# rekick2015-Prototyp-Tests.net
KiCad netlist of a schematic drawn in EAGLE
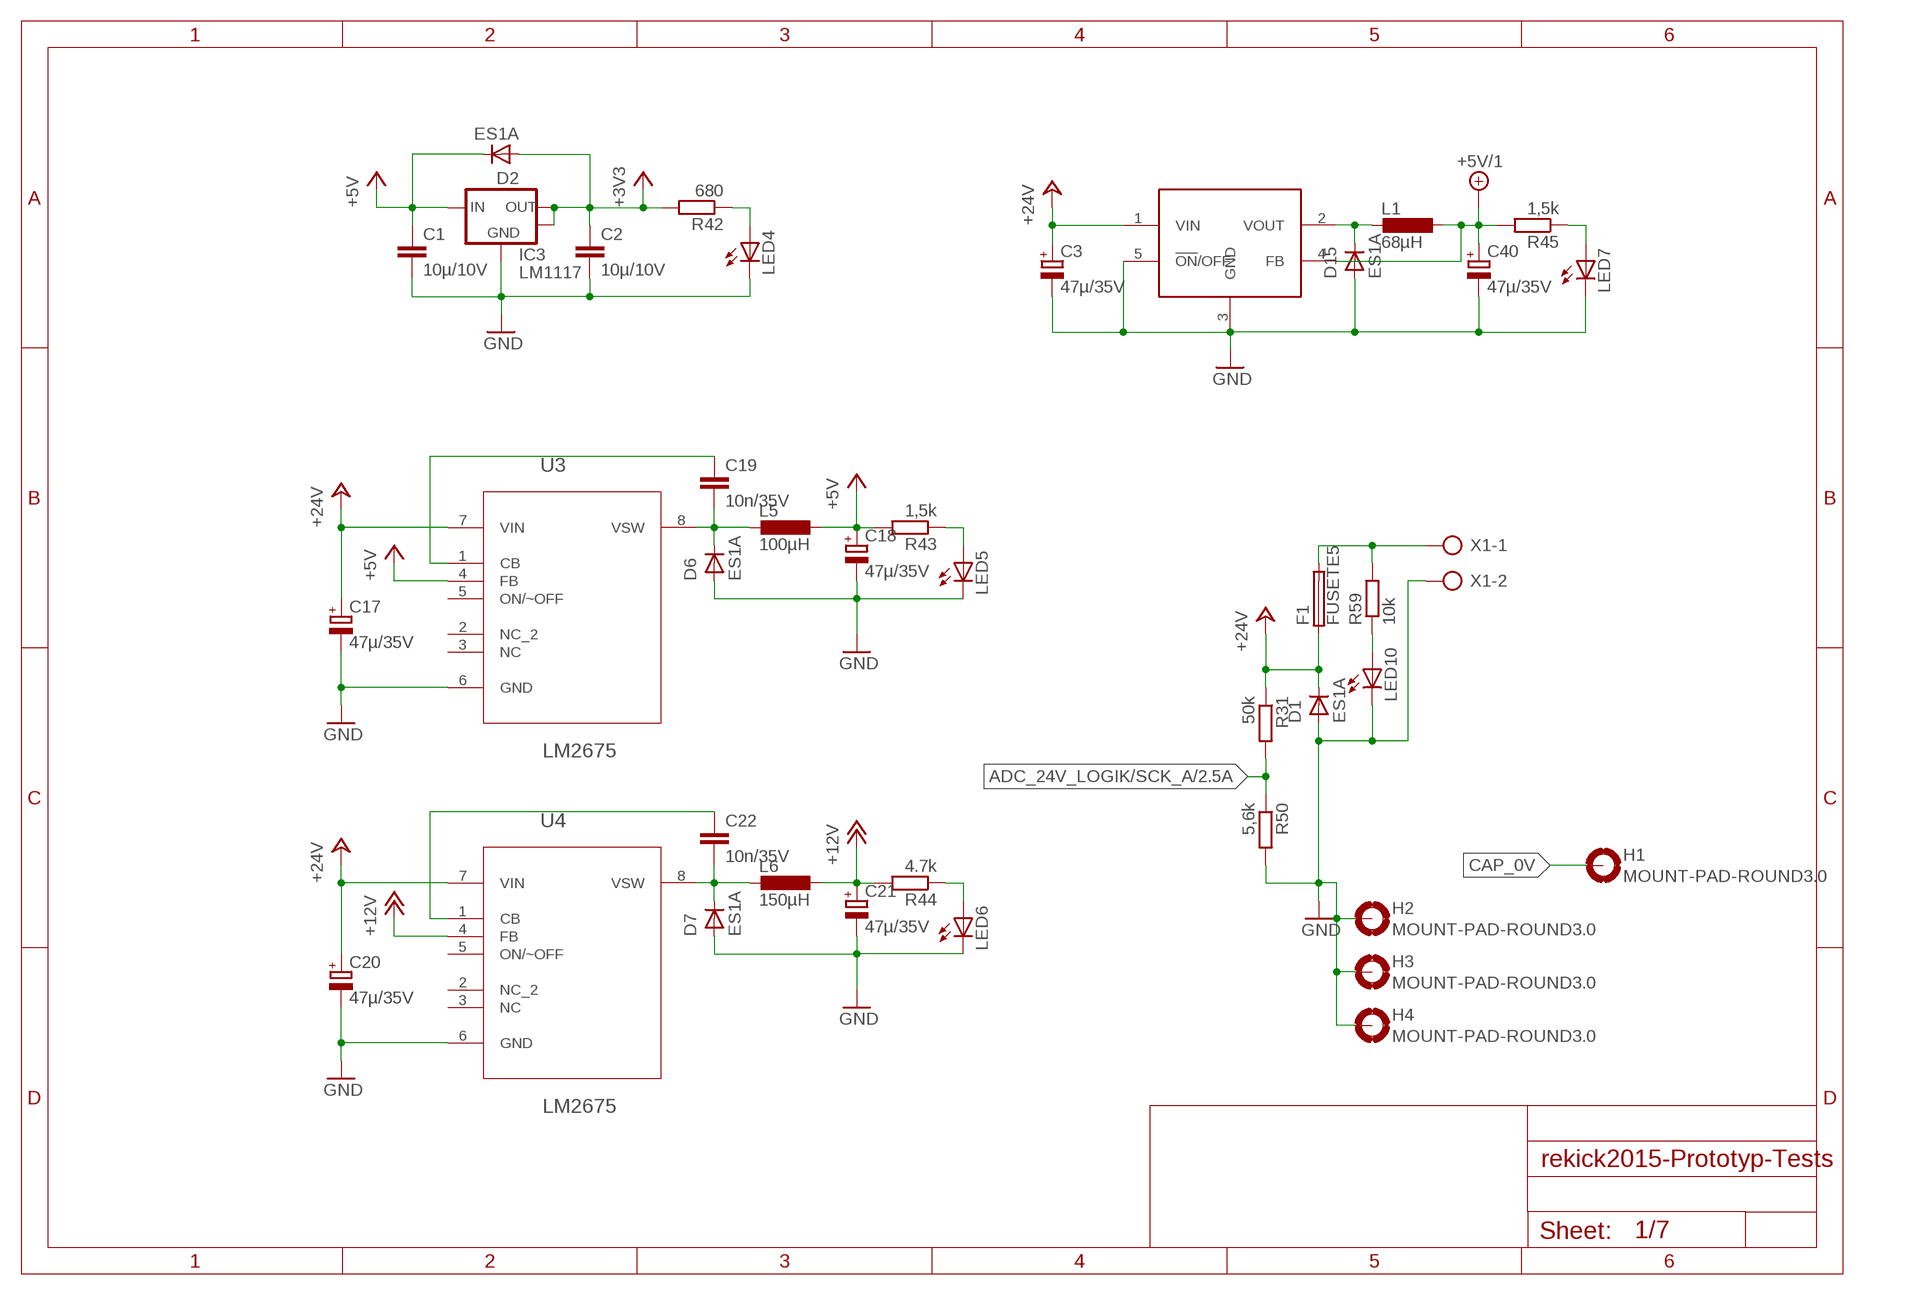
[diagram p0: schematic, sheet 1]
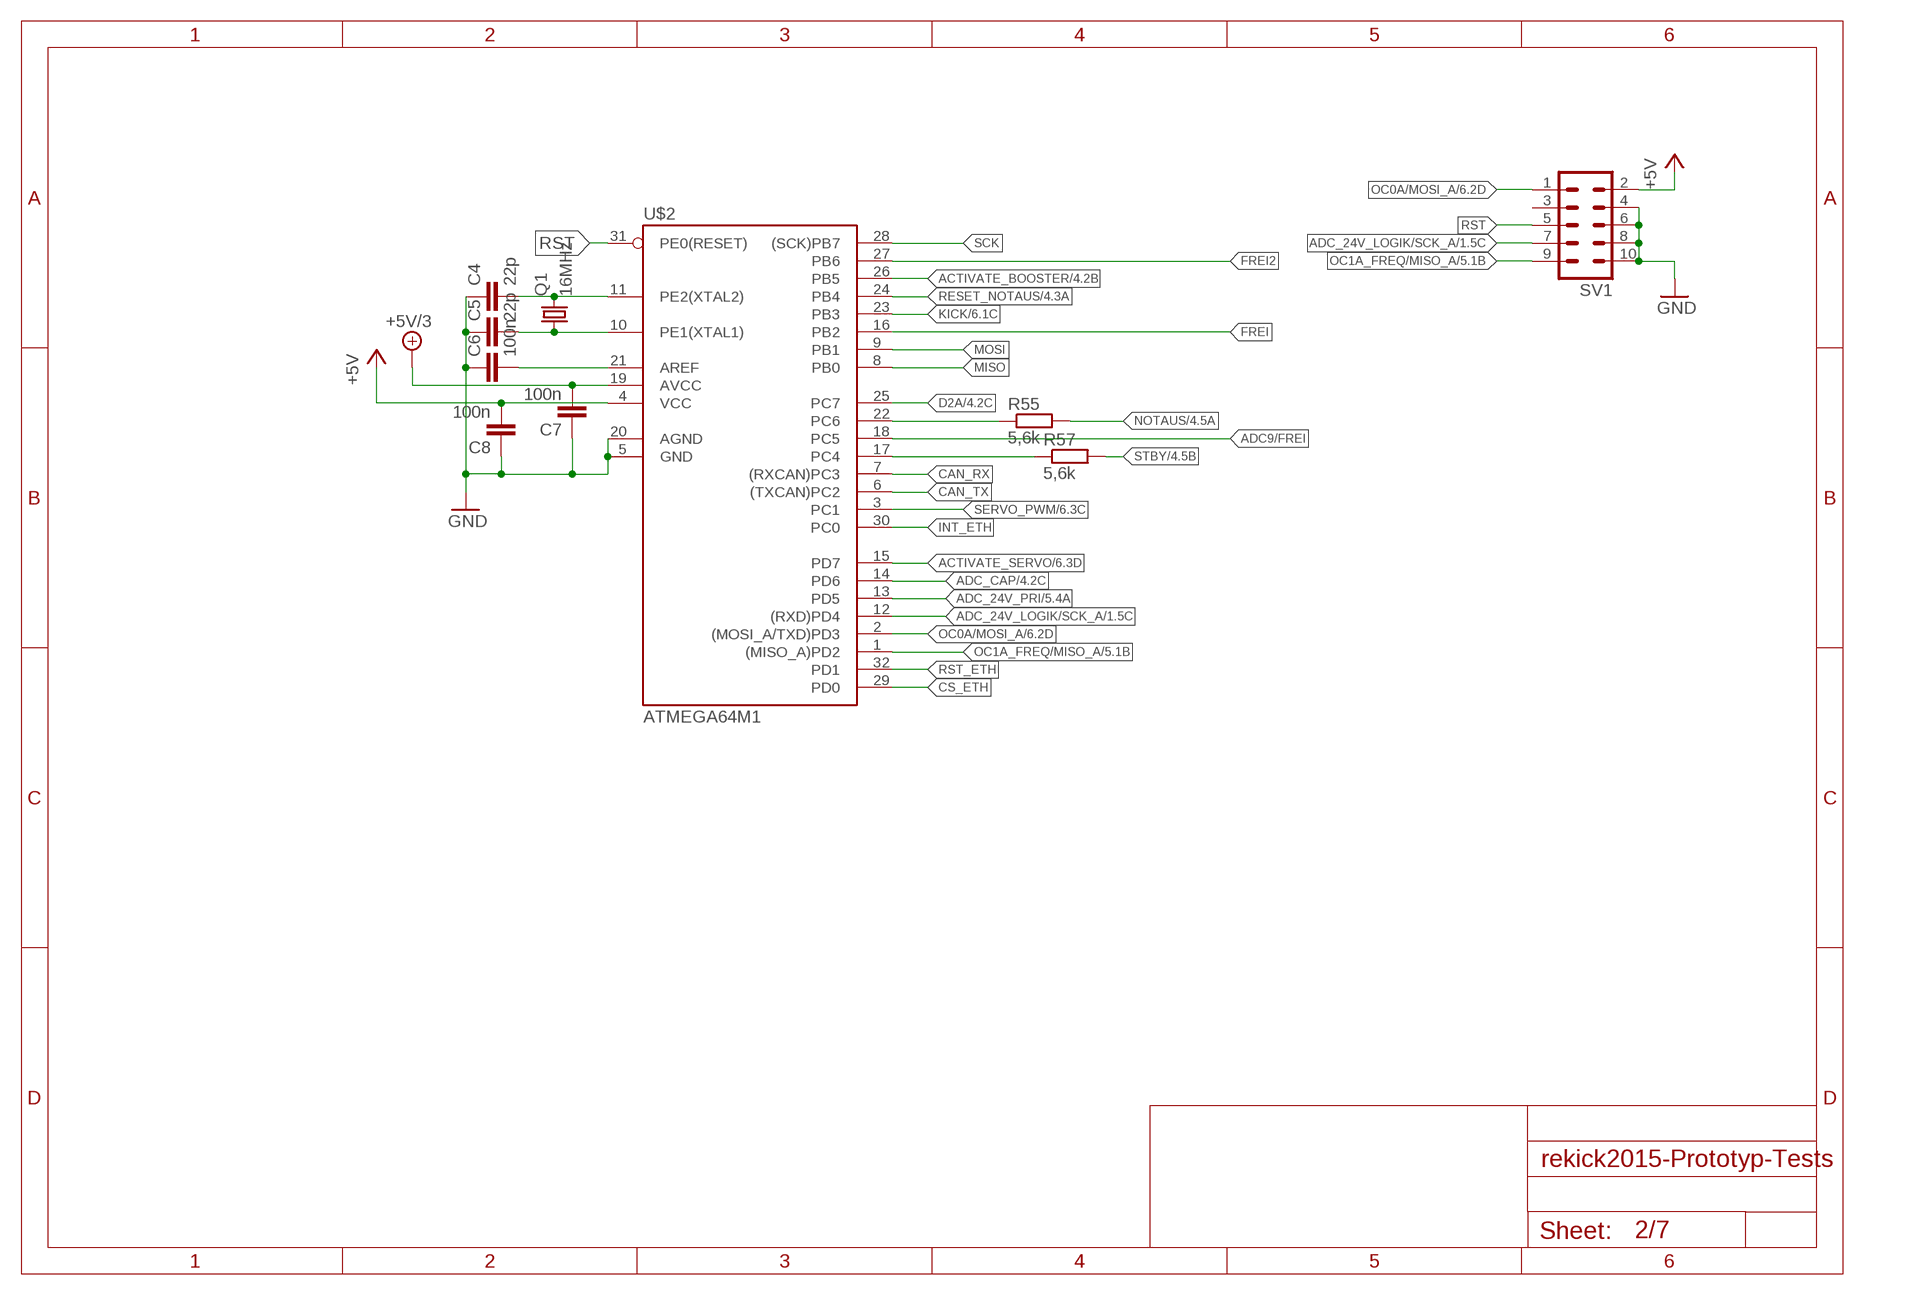
[diagram p1: schematic, sheet 2]
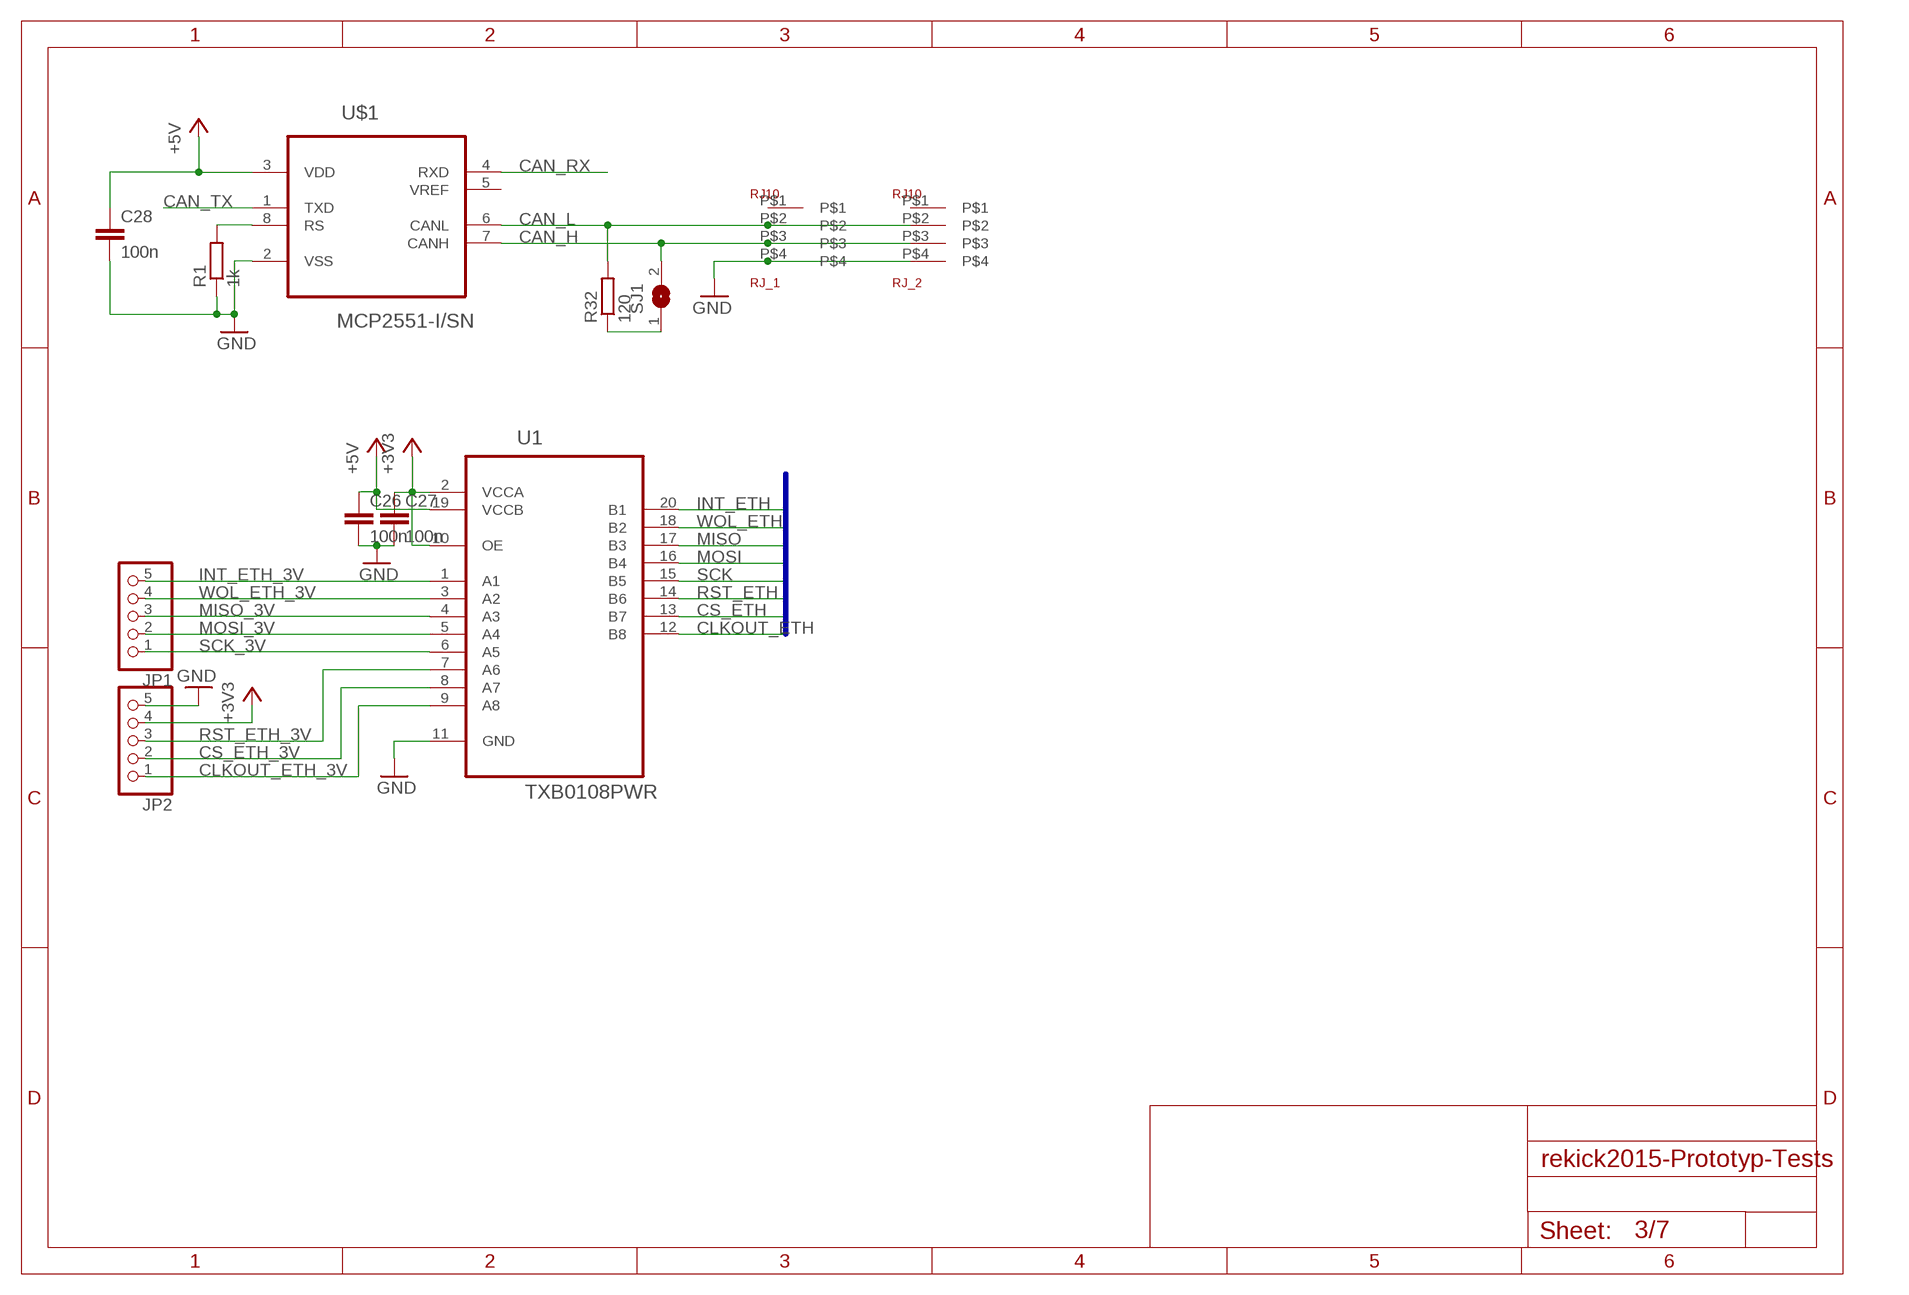
[diagram p2: schematic, sheet 3]
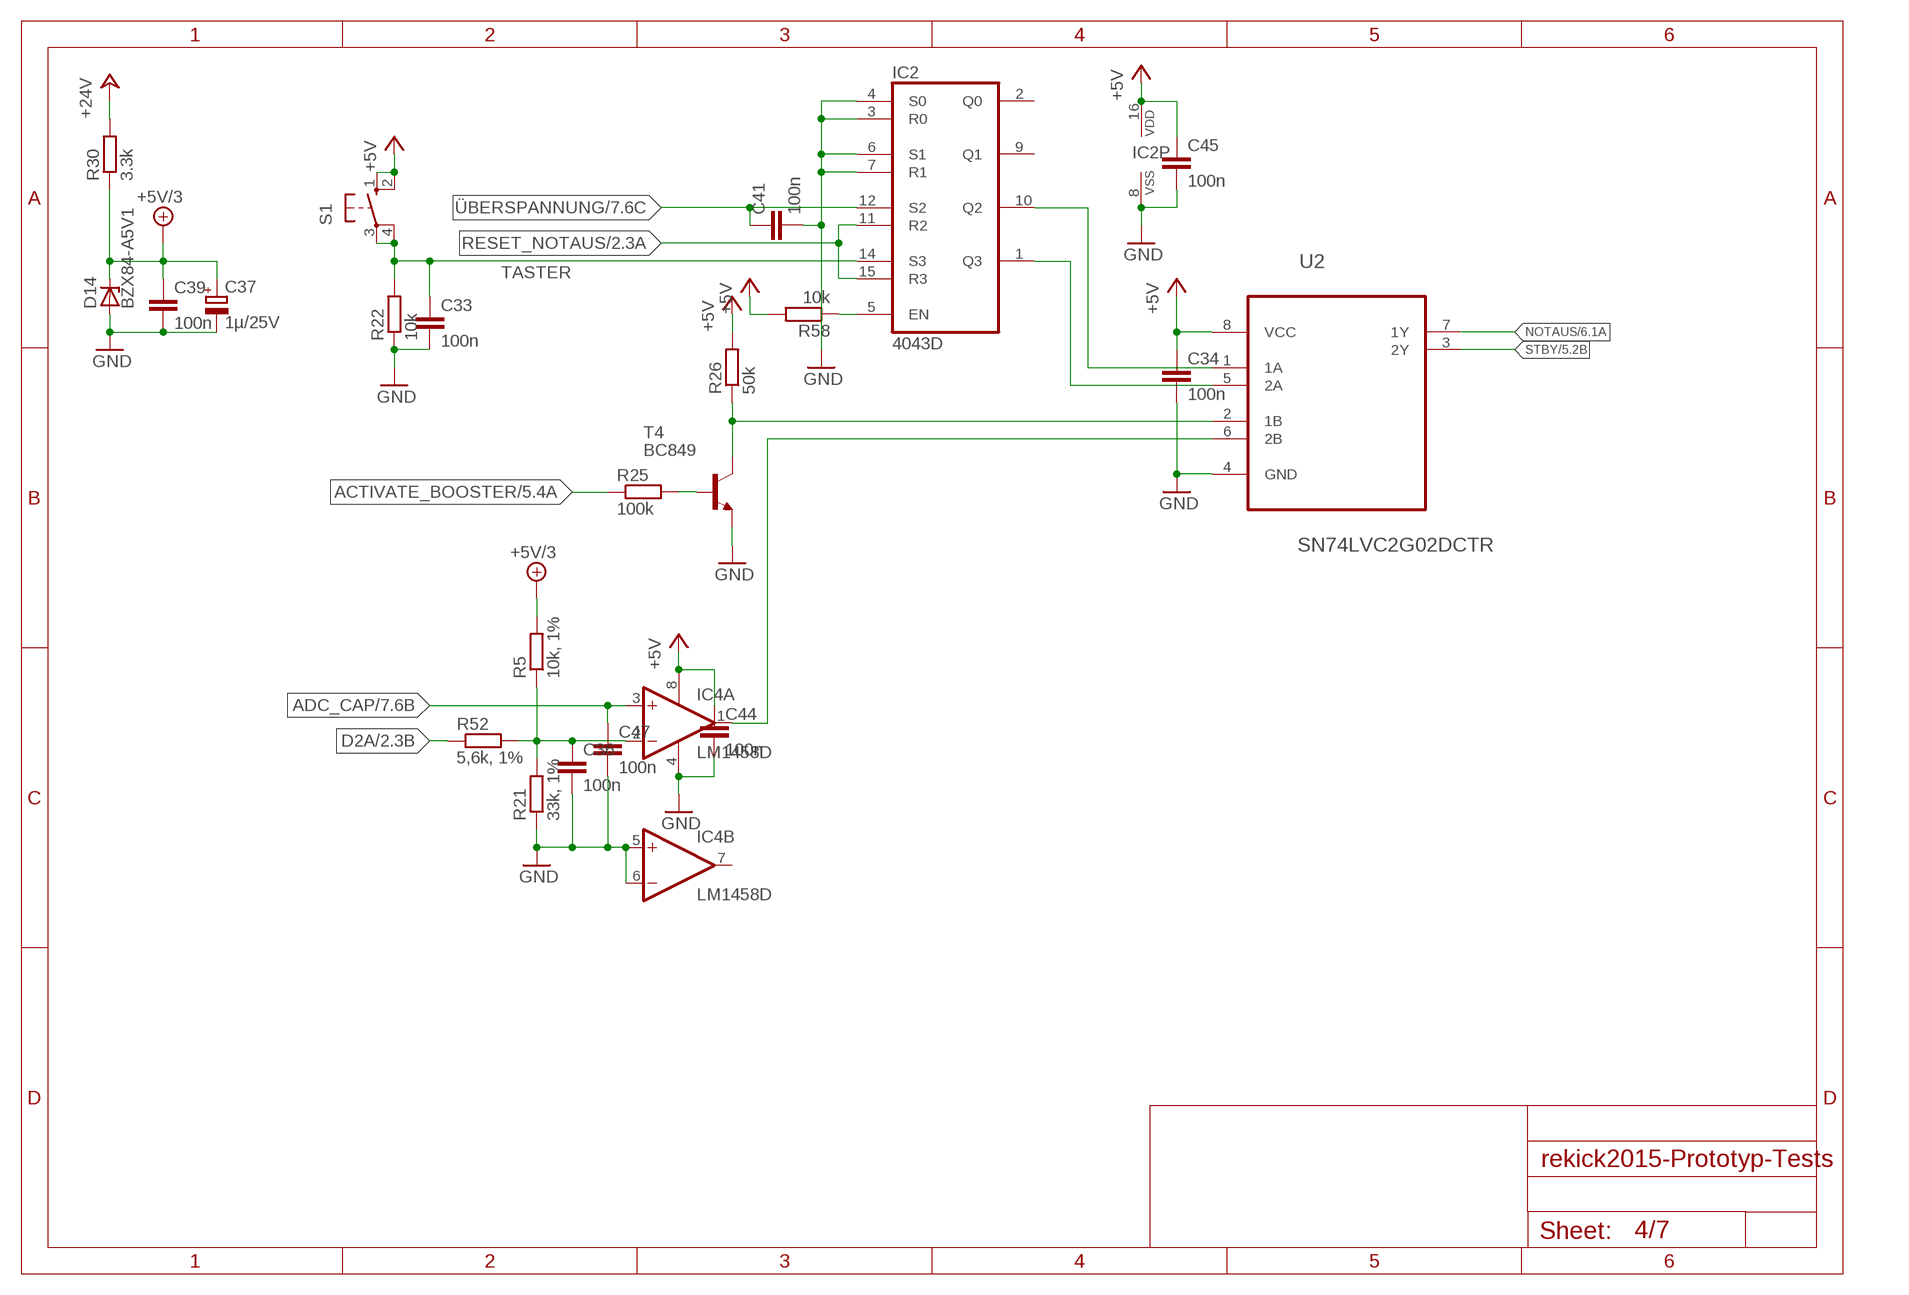
[diagram p3: schematic, sheet 4]
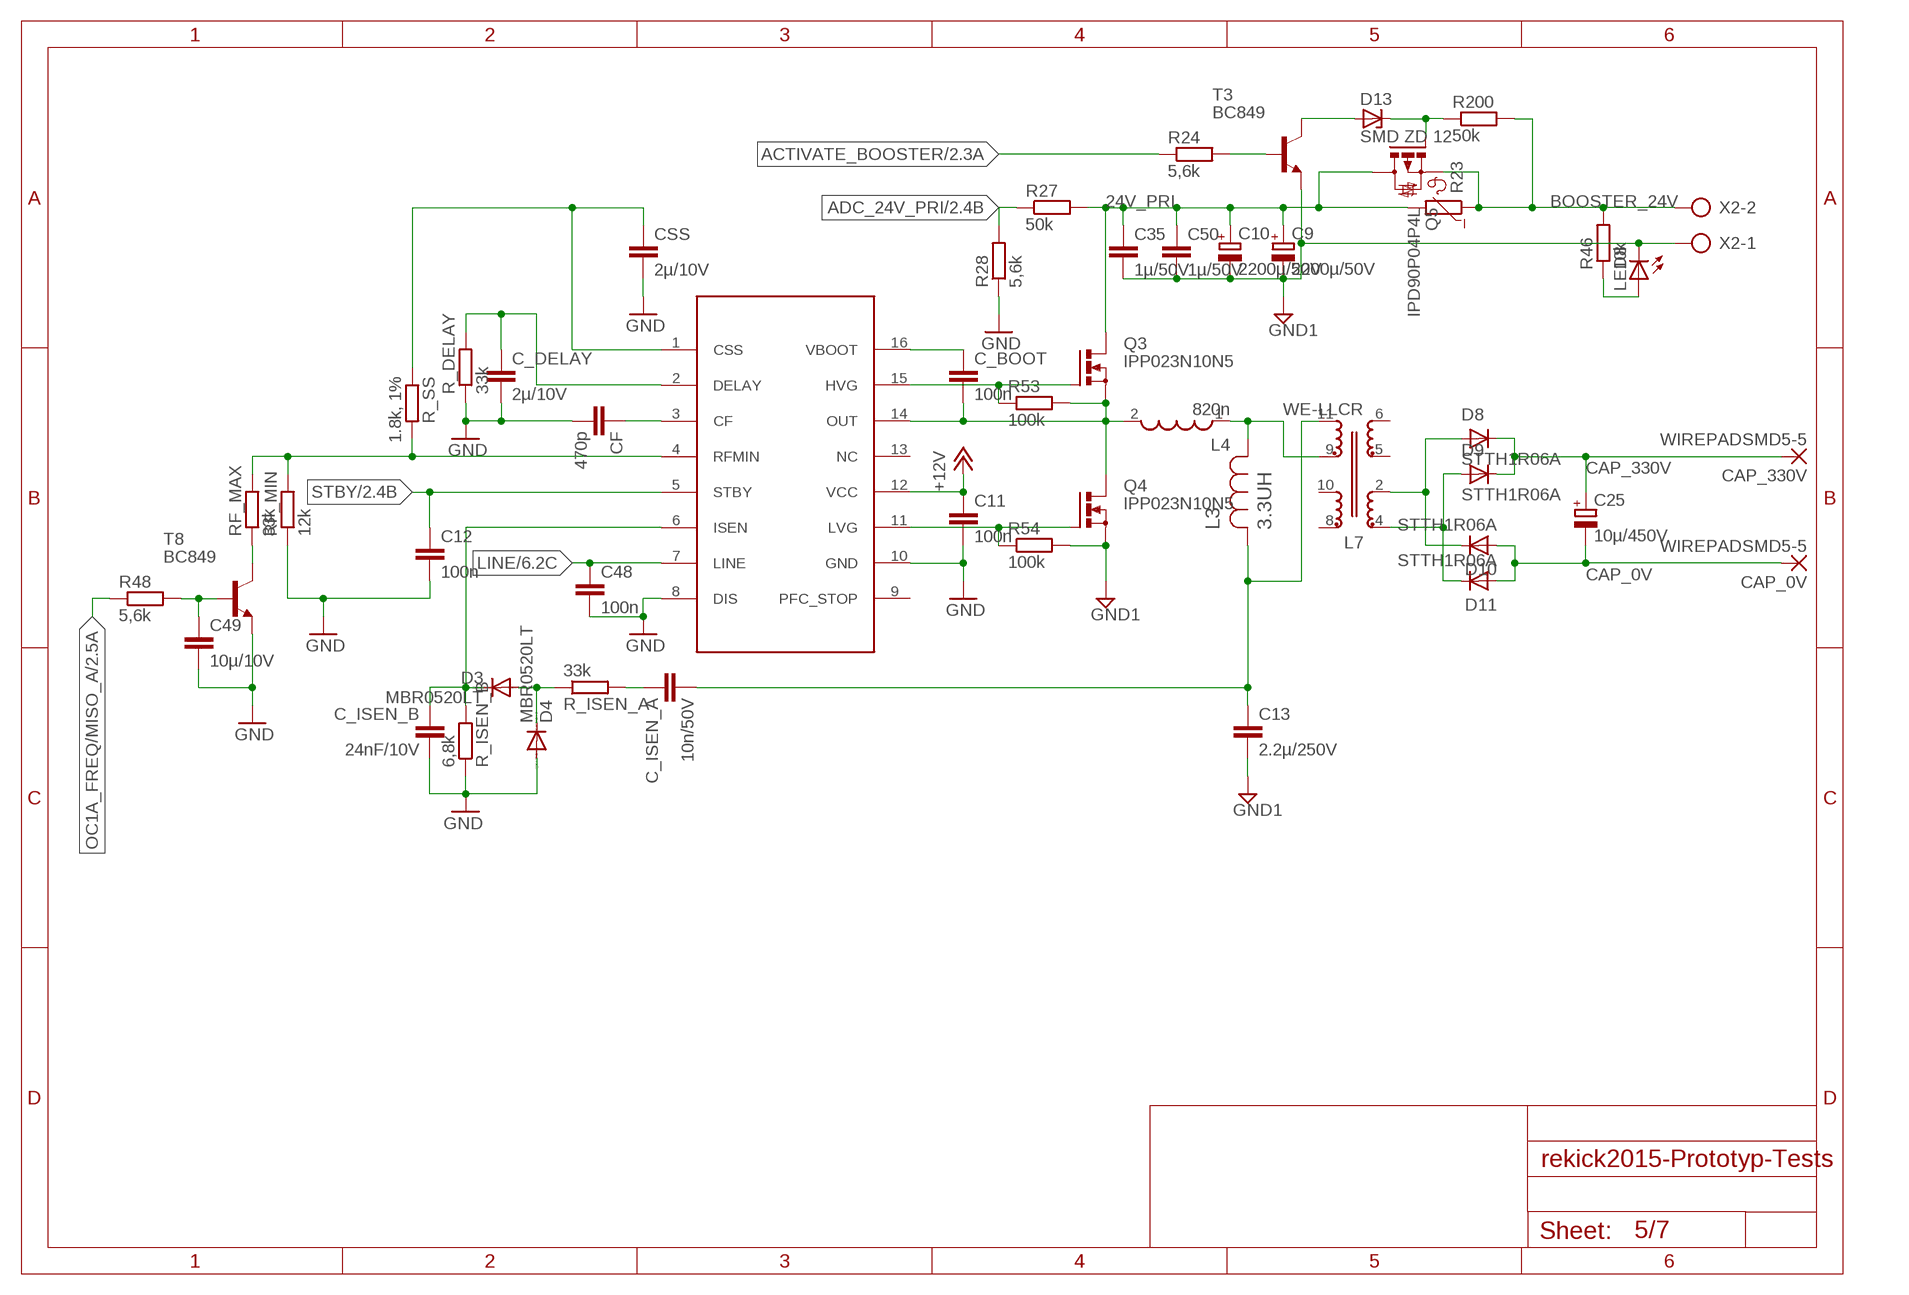
[diagram p4: schematic, sheet 5]
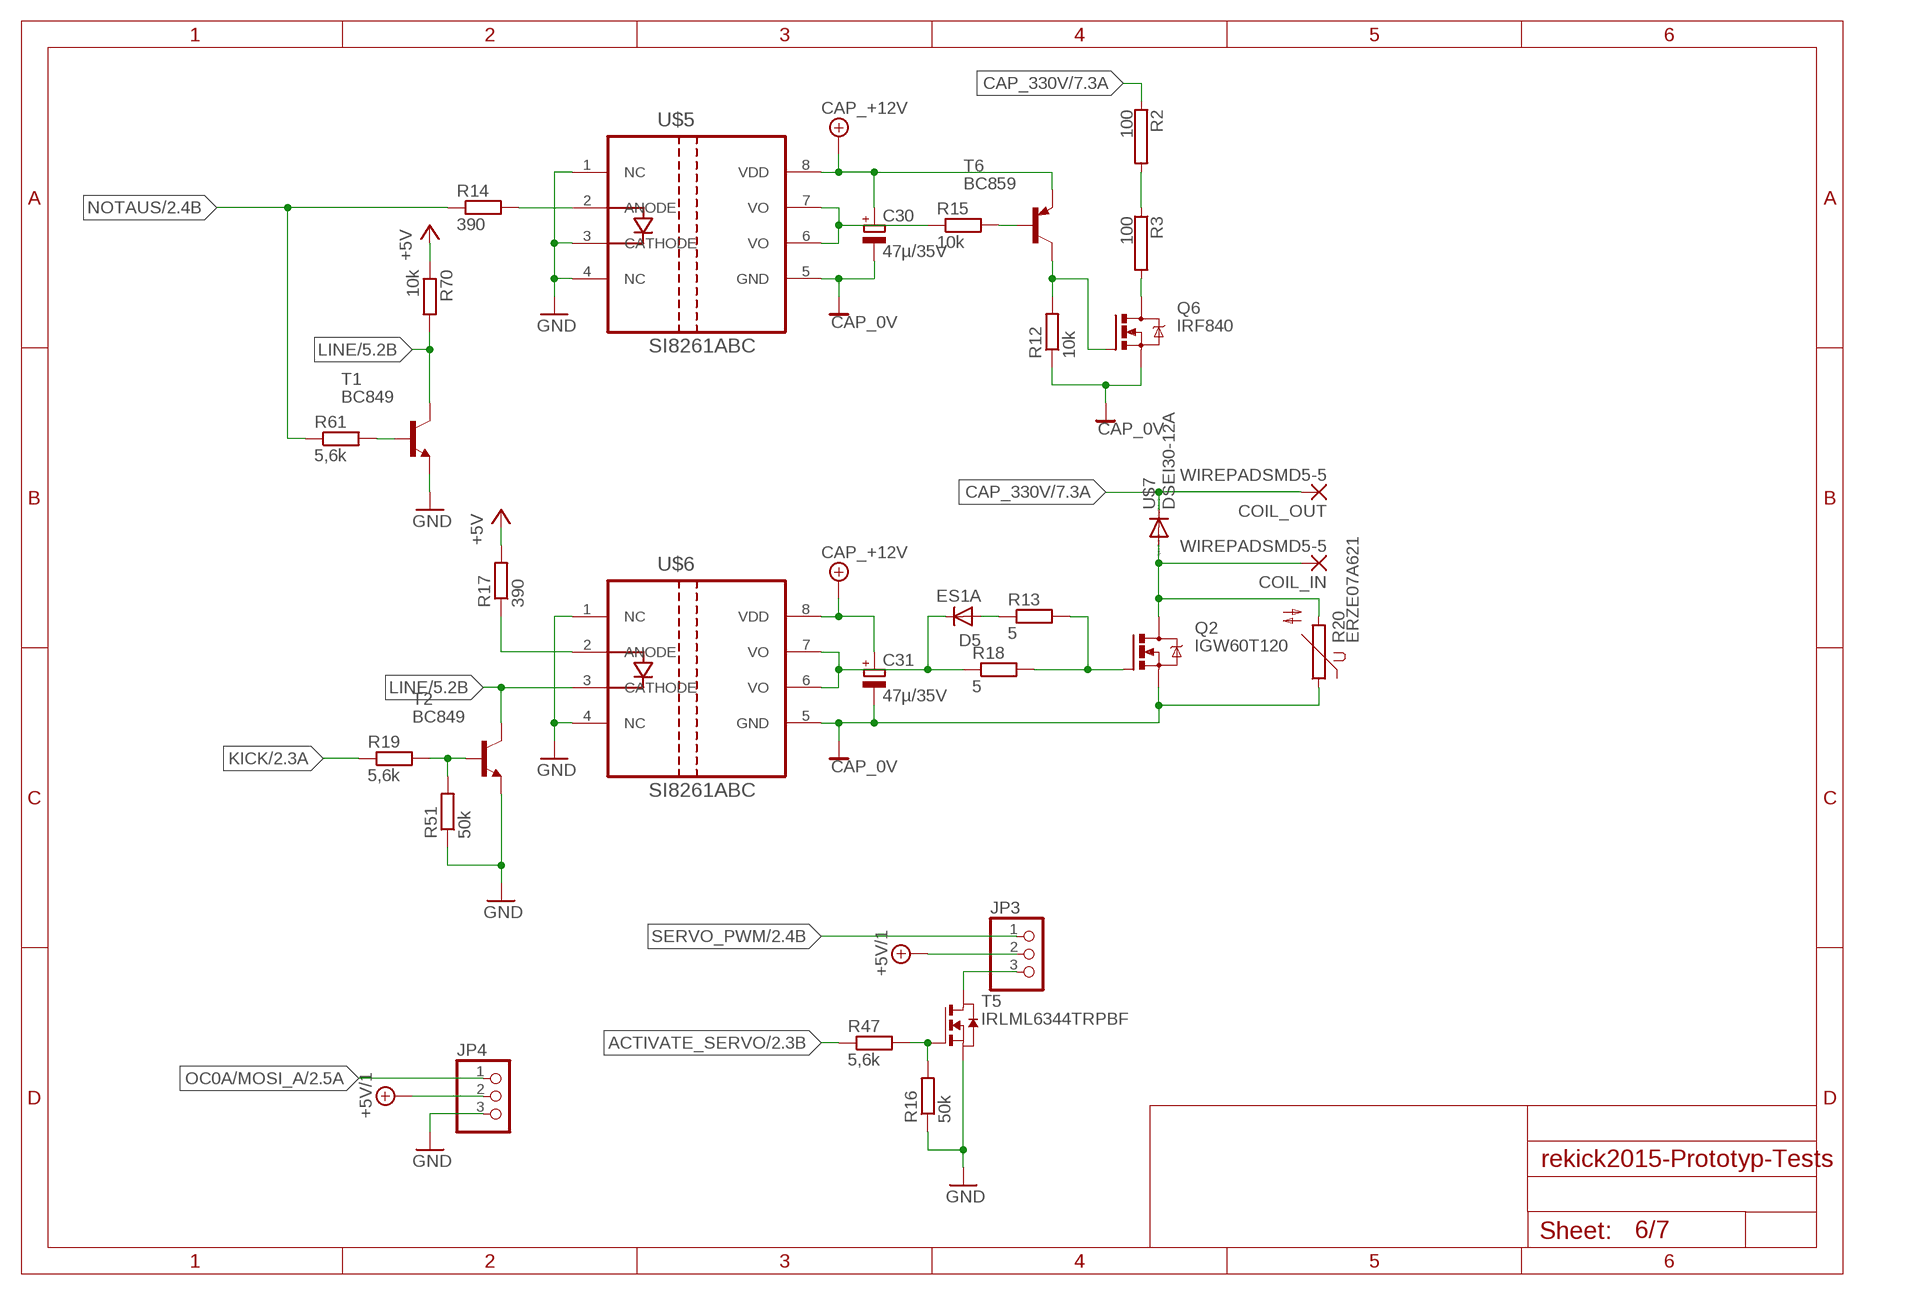
[diagram p5: schematic, sheet 6]
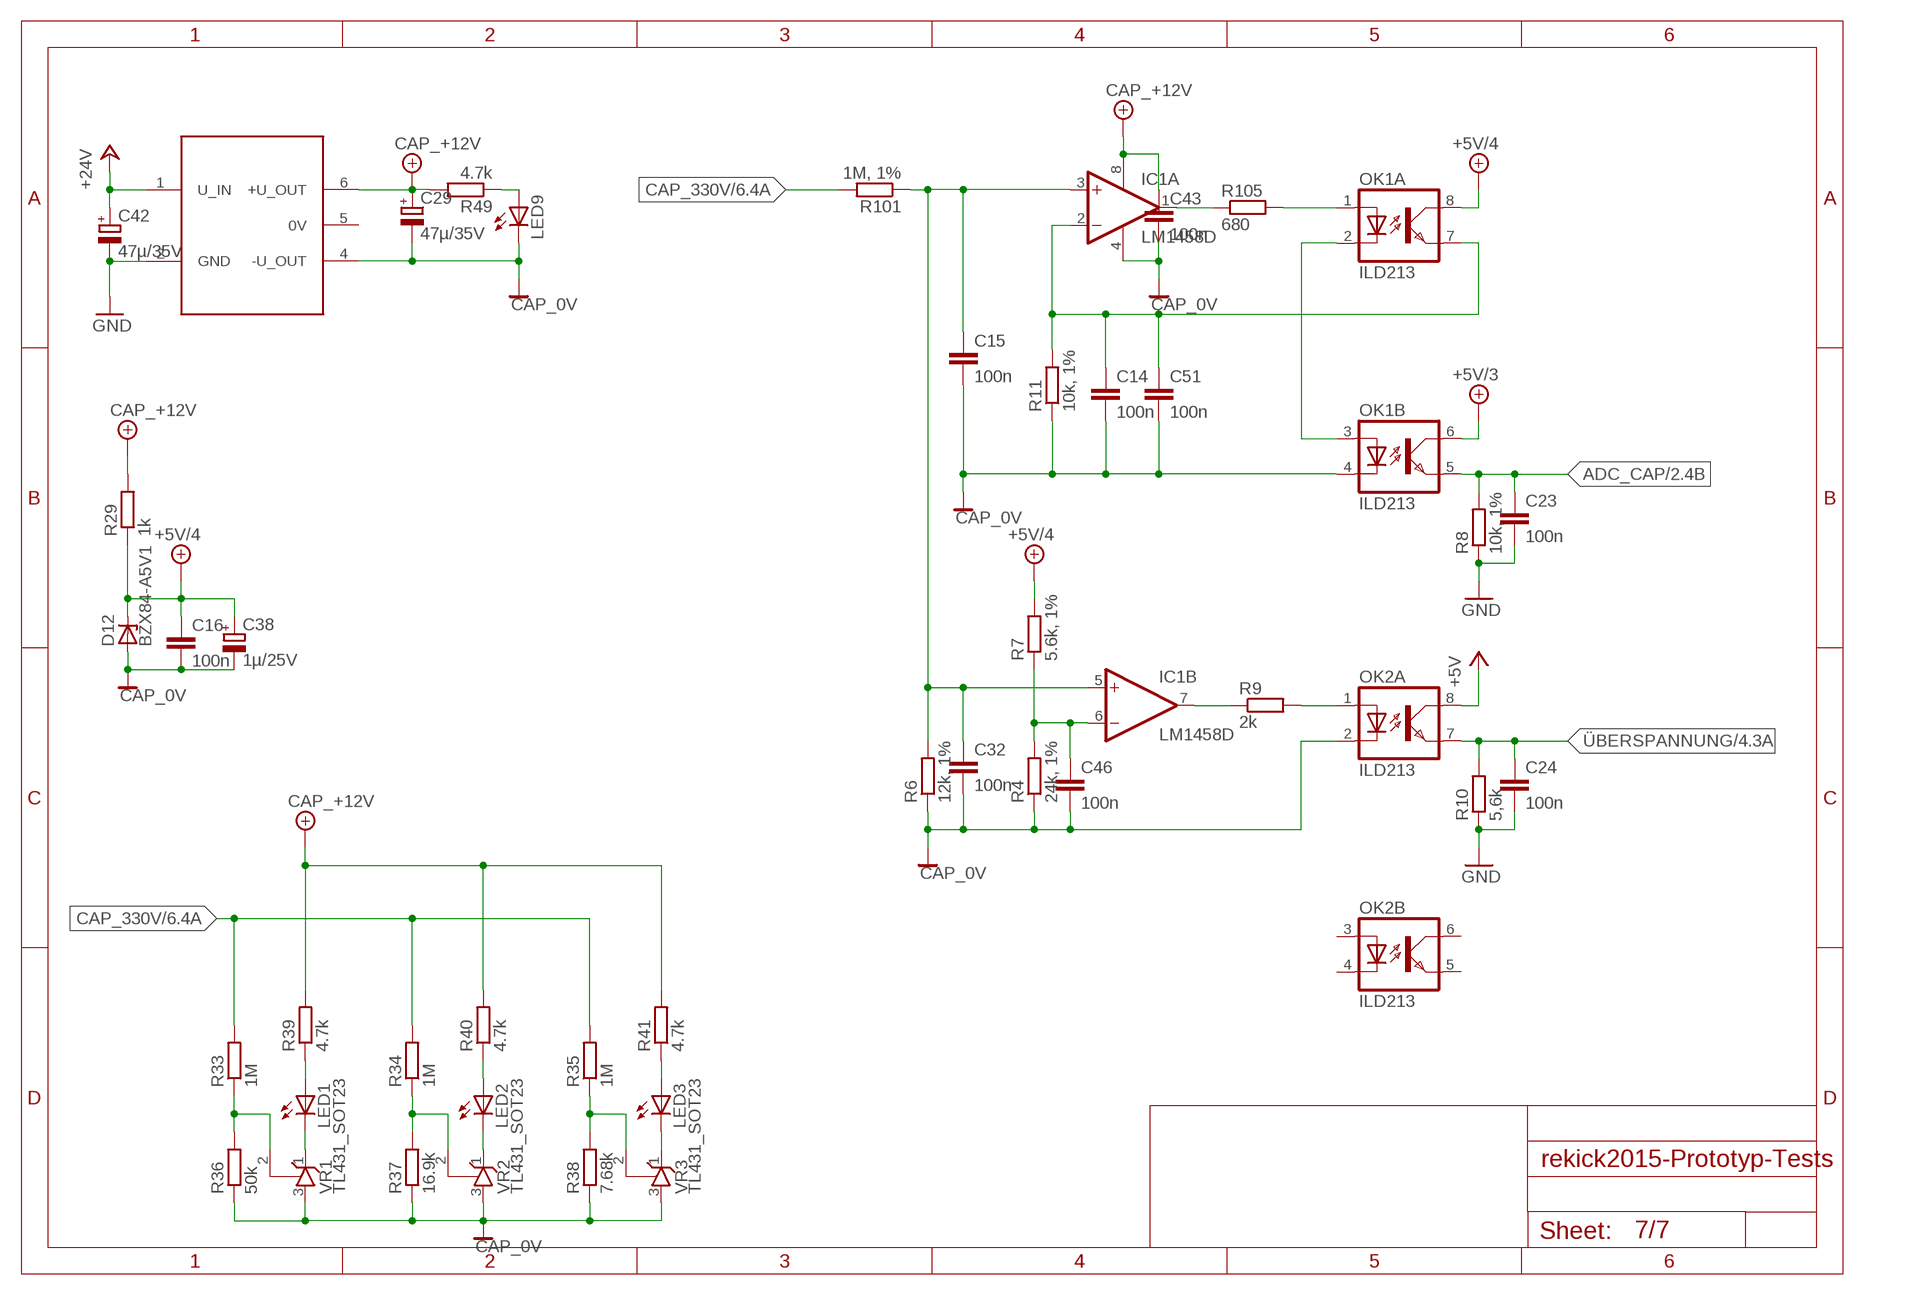
[diagram p6: schematic, sheet 7]

(export (version "E")
  (design (tool "Eeschema 10.0.6"))
  (components
    (comp (ref "C4")
      (value "22p")
      (footprint "eagle-import:C0603")
      (libsource (lib "eagle-import") (part "C-EUC0603"))
    )
    (comp (ref "C5")
      (value "22p")
      (footprint "eagle-import:C0603")
      (libsource (lib "eagle-import") (part "C-EUC0603"))
    )
    (comp (ref "C6")
      (value "100n")
      (footprint "eagle-import:C0603")
      (libsource (lib "eagle-import") (part "C-EUC0603"))
    )
    (comp (ref "C7")
      (value "100n")
      (footprint "eagle-import:C0603")
      (libsource (lib "eagle-import") (part "C-EUC0603"))
    )
    (comp (ref "C8")
      (value "100n")
      (footprint "eagle-import:C0603")
      (libsource (lib "eagle-import") (part "C-EUC0603"))
    )
    (comp (ref "Q1")
      (value "16MHz")
      (footprint "eagle-import:HC49UP")
      (libsource (lib "eagle-import") (part "CRYSTALHC49UP"))
    )
    (comp (ref "R55")
      (value "5,6k")
      (footprint "eagle-import:R0805")
      (libsource (lib "eagle-import") (part "R-EU_R0805"))
    )
    (comp (ref "R57")
      (value "5,6k")
      (footprint "eagle-import:R0805")
      (libsource (lib "eagle-import") (part "R-EU_R0805"))
    )
    (comp (ref "SV1")
      (value "ML10")
      (footprint "eagle-import:ML10")
      (libsource (lib "eagle-import") (part "ML10"))
    )
    (comp (ref "U$2")
      (value "ATMEGA64M1")
      (footprint "eagle-import:TQFP32-08")
      (libsource (lib "eagle-import") (part "ATMEGA64M1"))
    )
    (comp (ref "C9")
      (value "2200µ/50V")
      (footprint "eagle-import:E5-13")
      (libsource (lib "eagle-import") (part "CPOL-EUE5-13"))
    )
    (comp (ref "C10")
      (value "2200µ/50V")
      (footprint "eagle-import:E5-13")
      (libsource (lib "eagle-import") (part "CPOL-EUE5-13"))
    )
    (comp (ref "C11")
      (value "100n")
      (footprint "eagle-import:C0603")
      (libsource (lib "eagle-import") (part "C-EUC0603"))
    )
    (comp (ref "C12")
      (value "100n")
      (footprint "eagle-import:C0603")
      (libsource (lib "eagle-import") (part "C-EUC0603"))
    )
    (comp (ref "C13")
      (value "2.2µ/250V")
      (footprint "eagle-import:C2220K")
      (libsource (lib "eagle-import") (part "C-EUC2220K"))
    )
    (comp (ref "C25")
      (value "10µ/450V")
      (footprint "eagle-import:E5-10,5")
      (libsource (lib "eagle-import") (part "CPOL-EUE5-10.5"))
    )
    (comp (ref "C35")
      (value "1µ/50V")
      (footprint "eagle-import:C1206")
      (libsource (lib "eagle-import") (part "C-EUC1206"))
    )
    (comp (ref "C48")
      (value "100n")
      (footprint "eagle-import:C0603")
      (libsource (lib "eagle-import") (part "C-EUC0603"))
    )
    (comp (ref "C49")
      (value "10µ/10V")
      (footprint "eagle-import:C0603")
      (libsource (lib "eagle-import") (part "C-EUC0603"))
    )
    (comp (ref "C50")
      (value "1µ/50V")
      (footprint "eagle-import:C1206")
      (libsource (lib "eagle-import") (part "C-EUC1206"))
    )
    (comp (ref "CAP_0V")
      (value "WIREPADSMD5-5")
      (footprint "eagle-import:5-5")
      (libsource (lib "eagle-import") (part "WIREPADSMD5-5"))
    )
    (comp (ref "CAP_330V")
      (value "WIREPADSMD5-5")
      (footprint "eagle-import:5-5")
      (libsource (lib "eagle-import") (part "WIREPADSMD5-5"))
    )
    (comp (ref "CF")
      (value "470p")
      (footprint "eagle-import:C0603")
      (libsource (lib "eagle-import") (part "C-EUC0603"))
    )
    (comp (ref "CSS")
      (value "2µ/10V")
      (footprint "eagle-import:C0603")
      (libsource (lib "eagle-import") (part "C-EUC0603"))
    )
    (comp (ref "C_BOOT")
      (value "100n")
      (footprint "eagle-import:C0603")
      (libsource (lib "eagle-import") (part "C-EUC0603"))
    )
    (comp (ref "C_DELAY")
      (value "2µ/10V")
      (footprint "eagle-import:C0603")
      (libsource (lib "eagle-import") (part "C-EUC0603"))
    )
    (comp (ref "C_ISEN_A")
      (value "10n/50V")
      (footprint "eagle-import:C0603")
      (libsource (lib "eagle-import") (part "C-EUC0603"))
    )
    (comp (ref "C_ISEN_B")
      (value "24nF/10V")
      (footprint "eagle-import:C0603")
      (libsource (lib "eagle-import") (part "C-EUC0603"))
    )
    (comp (ref "D3")
      (value "MBR0520LT")
      (footprint "eagle-import:SOD123")
      (libsource (lib "eagle-import") (part "MBR0520LT"))
    )
    (comp (ref "D4")
      (value "MBR0520LT")
      (footprint "eagle-import:SOD123")
      (libsource (lib "eagle-import") (part "MBR0520LT"))
    )
    (comp (ref "D8")
      (value "STTH1R06A")
      (footprint "eagle-import:SMA-DO214AC")
      (libsource (lib "eagle-import") (part "GF1"))
    )
    (comp (ref "D9")
      (value "STTH1R06A")
      (footprint "eagle-import:SMA-DO214AC")
      (libsource (lib "eagle-import") (part "GF1"))
    )
    (comp (ref "D10")
      (value "STTH1R06A")
      (footprint "eagle-import:SMA-DO214AC")
      (libsource (lib "eagle-import") (part "GF1"))
    )
    (comp (ref "D11")
      (value "STTH1R06A")
      (footprint "eagle-import:SMA-DO214AC")
      (libsource (lib "eagle-import") (part "GF1"))
    )
    (comp (ref "D13")
      (value "SMD ZD 12")
      (footprint "eagle-import:TO236")
      (libsource (lib "eagle-import") (part "BZX84CSMD"))
    )
    (comp (ref "L3")
      (value "3.3UH")
      (footprint "eagle-import:IND_ELLATP-B")
      (fields (field (name "MPN") "ELLATP3R3NB"))
      (libsource (lib "eagle-import") (part "ELL-ATP-BATP3R3NB"))
    )
    (comp (ref "L4")
      (value "820n")
      (footprint "eagle-import:WE-HCI_1890")
      (libsource (lib "eagle-import") (part "WE-HCI_1890"))
    )
    (comp (ref "L7")
      (value "WE-LLCR")
      (footprint "eagle-import:WE-LLCR_ETD34")
      (libsource (lib "eagle-import") (part "WE-LLCR_ETD34"))
    )
    (comp (ref "LED8")
      (value "LEDCHIP-LED0805")
      (footprint "eagle-import:CHIP-LED0805")
      (libsource (lib "eagle-import") (part "LEDCHIP-LED0805"))
    )
    (comp (ref "Q3")
      (value "IPP023N10N5")
      (footprint "eagle-import:TO220BV")
      (libsource (lib "eagle-import") (part "PMOSFET_NTO220BV"))
    )
    (comp (ref "Q4")
      (value "IPP023N10N5")
      (footprint "eagle-import:TO220BV")
      (libsource (lib "eagle-import") (part "PMOSFET_NTO220BV"))
    )
    (comp (ref "Q5")
      (value "IPD90P04P4L")
      (footprint "eagle-import:D-PAK_TO252AA")
      (libsource (lib "eagle-import") (part "IRF?5305R"))
    )
    (comp (ref "R23")
      (value "NTC644A")
      (footprint "eagle-import:N644A")
      (libsource (lib "eagle-import") (part "NTC644A"))
    )
    (comp (ref "R24")
      (value "5,6k")
      (footprint "eagle-import:R0805")
      (libsource (lib "eagle-import") (part "R-EU_R0805"))
    )
    (comp (ref "R27")
      (value "50k")
      (footprint "eagle-import:R0805")
      (libsource (lib "eagle-import") (part "R-EU_R0805"))
    )
    (comp (ref "R28")
      (value "5,6k")
      (footprint "eagle-import:R0805")
      (libsource (lib "eagle-import") (part "R-EU_R0805"))
    )
    (comp (ref "R46")
      (value "10k")
      (footprint "eagle-import:R0805")
      (libsource (lib "eagle-import") (part "R-EU_R0805"))
    )
    (comp (ref "R48")
      (value "5,6k")
      (footprint "eagle-import:R0805")
      (libsource (lib "eagle-import") (part "R-EU_R0805"))
    )
    (comp (ref "R53")
      (value "100k")
      (footprint "eagle-import:R0805")
      (libsource (lib "eagle-import") (part "R-EU_R0805"))
    )
    (comp (ref "R54")
      (value "100k")
      (footprint "eagle-import:R0805")
      (libsource (lib "eagle-import") (part "R-EU_R0805"))
    )
    (comp (ref "R200")
      (value "50k")
      (footprint "eagle-import:R0805")
      (libsource (lib "eagle-import") (part "R-EU_R0805"))
    )
    (comp (ref "RF_MAX")
      (value "33k")
      (footprint "eagle-import:R0805")
      (libsource (lib "eagle-import") (part "R-EU_R0805"))
    )
    (comp (ref "RF_MIN")
      (value "12k")
      (footprint "eagle-import:R0805")
      (libsource (lib "eagle-import") (part "R-EU_R0805"))
    )
    (comp (ref "R_DELAY")
      (value "33k")
      (footprint "eagle-import:R0805")
      (libsource (lib "eagle-import") (part "R-EU_R0805"))
    )
    (comp (ref "R_ISEN_A")
      (value "33k")
      (footprint "eagle-import:R0805")
      (libsource (lib "eagle-import") (part "R-EU_R0805"))
    )
    (comp (ref "R_ISEN_B")
      (value "6,8k")
      (footprint "eagle-import:R0805")
      (libsource (lib "eagle-import") (part "R-EU_R0805"))
    )
    (comp (ref "R_SS")
      (value "1.8k, 1%")
      (footprint "eagle-import:R0805")
      (libsource (lib "eagle-import") (part "R-EU_R0805"))
    )
    (comp (ref "T3")
      (value "BC849")
      (footprint "eagle-import:SOT23")
      (libsource (lib "eagle-import") (part "BC849"))
    )
    (comp (ref "T8")
      (value "BC849")
      (footprint "eagle-import:SOT23")
      (libsource (lib "eagle-import") (part "BC849"))
    )
    (comp (ref "U$3")
      (value "L6599")
      (footprint "eagle-import:SO16")
      (libsource (lib "eagle-import") (part "L6599"))
    )
    (comp (ref "X2")
      (value "AK500/2-H")
      (footprint "eagle-import:AK500_2-H")
      (libsource (lib "eagle-import") (part "AK500/2-H"))
    )
    (comp (ref "C14")
      (value "100n")
      (footprint "eagle-import:C0603")
      (libsource (lib "eagle-import") (part "C-EUC0603"))
    )
    (comp (ref "C15")
      (value "100n")
      (footprint "eagle-import:C0603")
      (libsource (lib "eagle-import") (part "C-EUC0603"))
    )
    (comp (ref "C16")
      (value "100n")
      (footprint "eagle-import:C0603")
      (libsource (lib "eagle-import") (part "C-EUC0603"))
    )
    (comp (ref "C23")
      (value "100n")
      (footprint "eagle-import:C0603")
      (libsource (lib "eagle-import") (part "C-EUC0603"))
    )
    (comp (ref "C24")
      (value "100n")
      (footprint "eagle-import:C0603")
      (libsource (lib "eagle-import") (part "C-EUC0603"))
    )
    (comp (ref "C29")
      (value "47µ/35V")
      (footprint "eagle-import:PANASONIC_D")
      (libsource (lib "eagle-import") (part "CPOL-EUD"))
    )
    (comp (ref "C32")
      (value "100n")
      (footprint "eagle-import:C0603")
      (libsource (lib "eagle-import") (part "C-EUC0603"))
    )
    (comp (ref "C38")
      (value "1µ/25V")
      (footprint "eagle-import:SMC_A")
      (libsource (lib "eagle-import") (part "CPOL-EUSMCA"))
    )
    (comp (ref "C42")
      (value "47µ/35V")
      (footprint "eagle-import:PANASONIC_D")
      (libsource (lib "eagle-import") (part "CPOL-EUD"))
    )
    (comp (ref "C43")
      (value "100n")
      (footprint "eagle-import:C0603")
      (libsource (lib "eagle-import") (part "C-EUC0603"))
    )
    (comp (ref "C46")
      (value "100n")
      (footprint "eagle-import:C0603")
      (libsource (lib "eagle-import") (part "C-EUC0603"))
    )
    (comp (ref "C51")
      (value "100n")
      (footprint "eagle-import:C0603")
      (libsource (lib "eagle-import") (part "C-EUC0603"))
    )
    (comp (ref "D12")
      (value "BZX84-A5V1")
      (footprint "eagle-import:TO236")
      (libsource (lib "eagle-import") (part "BZX84CSMD"))
    )
    (comp (ref "IC1")
      (value "LM1458D")
      (footprint "eagle-import:SO08")
      (libsource (lib "eagle-import") (part "1458DLM"))
    )
    (comp (ref "LED1")
      (value "LEDCHIP-LED0805")
      (footprint "eagle-import:CHIP-LED0805")
      (libsource (lib "eagle-import") (part "LEDCHIP-LED0805"))
    )
    (comp (ref "LED2")
      (value "LEDCHIP-LED0805")
      (footprint "eagle-import:CHIP-LED0805")
      (libsource (lib "eagle-import") (part "LEDCHIP-LED0805"))
    )
    (comp (ref "LED3")
      (value "LEDCHIP-LED0805")
      (footprint "eagle-import:CHIP-LED0805")
      (libsource (lib "eagle-import") (part "LEDCHIP-LED0805"))
    )
    (comp (ref "LED9")
      (value "LEDCHIP-LED0805")
      (footprint "eagle-import:CHIP-LED0805")
      (libsource (lib "eagle-import") (part "LEDCHIP-LED0805"))
    )
    (comp (ref "OK1")
      (value "ILD213")
      (footprint "eagle-import:SOIC08")
      (libsource (lib "eagle-import") (part "ILD213"))
    )
    (comp (ref "OK2")
      (value "ILD213")
      (footprint "eagle-import:SOIC08")
      (libsource (lib "eagle-import") (part "ILD213"))
    )
    (comp (ref "R4")
      (value "24k, 1%")
      (footprint "eagle-import:R0805")
      (libsource (lib "eagle-import") (part "R-EU_R0805"))
    )
    (comp (ref "R6")
      (value "12k, 1%")
      (footprint "eagle-import:R0805")
      (libsource (lib "eagle-import") (part "R-EU_R0805"))
    )
    (comp (ref "R7")
      (value "5.6k, 1%")
      (footprint "eagle-import:R0805")
      (libsource (lib "eagle-import") (part "R-EU_R0805"))
    )
    (comp (ref "R8")
      (value "10k, 1%")
      (footprint "eagle-import:R0805")
      (libsource (lib "eagle-import") (part "R-EU_R0805"))
    )
    (comp (ref "R9")
      (value "2k")
      (footprint "eagle-import:R0805")
      (libsource (lib "eagle-import") (part "R-EU_R0805"))
    )
    (comp (ref "R10")
      (value "5,6k")
      (footprint "eagle-import:R0805")
      (libsource (lib "eagle-import") (part "R-EU_R0805"))
    )
    (comp (ref "R11")
      (value "10k, 1%")
      (footprint "eagle-import:R0805")
      (libsource (lib "eagle-import") (part "R-EU_R0805"))
    )
    (comp (ref "R29")
      (value "1k")
      (footprint "eagle-import:R0805")
      (libsource (lib "eagle-import") (part "R-EU_R0805"))
    )
    (comp (ref "R33")
      (value "1M")
      (footprint "eagle-import:R2512")
      (libsource (lib "eagle-import") (part "R-EU_R2512"))
    )
    (comp (ref "R34")
      (value "1M")
      (footprint "eagle-import:R2512")
      (libsource (lib "eagle-import") (part "R-EU_R2512"))
    )
    (comp (ref "R35")
      (value "1M")
      (footprint "eagle-import:R2512")
      (libsource (lib "eagle-import") (part "R-EU_R2512"))
    )
    (comp (ref "R36")
      (value "50k")
      (footprint "eagle-import:R0805")
      (libsource (lib "eagle-import") (part "R-EU_R0805"))
    )
    (comp (ref "R37")
      (value "16.9k")
      (footprint "eagle-import:R0805")
      (libsource (lib "eagle-import") (part "R-EU_R0805"))
    )
    (comp (ref "R38")
      (value "7.68k")
      (footprint "eagle-import:R0805")
      (libsource (lib "eagle-import") (part "R-EU_R0805"))
    )
    (comp (ref "R39")
      (value "4.7k")
      (footprint "eagle-import:R0805")
      (libsource (lib "eagle-import") (part "R-EU_R0805"))
    )
    (comp (ref "R40")
      (value "4.7k")
      (footprint "eagle-import:R0805")
      (libsource (lib "eagle-import") (part "R-EU_R0805"))
    )
    (comp (ref "R41")
      (value "4.7k")
      (footprint "eagle-import:R0805")
      (libsource (lib "eagle-import") (part "R-EU_R0805"))
    )
    (comp (ref "R49")
      (value "4.7k")
      (footprint "eagle-import:R0805")
      (libsource (lib "eagle-import") (part "R-EU_R0805"))
    )
    (comp (ref "R101")
      (value "1M, 1%")
      (footprint "eagle-import:R2512")
      (libsource (lib "eagle-import") (part "R-EU_R2512"))
    )
    (comp (ref "R105")
      (value "680")
      (footprint "eagle-import:R0805")
      (libsource (lib "eagle-import") (part "R-EU_R0805"))
    )
    (comp (ref "U$4")
      (value "TMH-D")
      (footprint "eagle-import:TMH-D")
      (libsource (lib "eagle-import") (part "TMH-D"))
    )
    (comp (ref "VR1")
      (value "TL431_SOT23")
      (footprint "eagle-import:SOT23")
      (libsource (lib "eagle-import") (part "TL431_SOT23"))
    )
    (comp (ref "VR2")
      (value "TL431_SOT23")
      (footprint "eagle-import:SOT23")
      (libsource (lib "eagle-import") (part "TL431_SOT23"))
    )
    (comp (ref "VR3")
      (value "TL431_SOT23")
      (footprint "eagle-import:SOT23")
      (libsource (lib "eagle-import") (part "TL431_SOT23"))
    )
    (comp (ref "C26")
      (value "100n")
      (footprint "eagle-import:C0603")
      (libsource (lib "eagle-import") (part "C-EUC0603"))
    )
    (comp (ref "C27")
      (value "100n")
      (footprint "eagle-import:C0603")
      (libsource (lib "eagle-import") (part "C-EUC0603"))
    )
    (comp (ref "C28")
      (value "100n")
      (footprint "eagle-import:C0603")
      (libsource (lib "eagle-import") (part "C-EUC0603"))
    )
    (comp (ref "JP1")
      (value "PINHD-1X5")
      (footprint "eagle-import:1X05")
      (libsource (lib "eagle-import") (part "PINHD-1X5"))
    )
    (comp (ref "JP2")
      (value "PINHD-1X5")
      (footprint "eagle-import:1X05")
      (libsource (lib "eagle-import") (part "PINHD-1X5"))
    )
    (comp (ref "R1")
      (value "1k")
      (footprint "eagle-import:R0805")
      (libsource (lib "eagle-import") (part "R-EU_R0805"))
    )
    (comp (ref "R32")
      (value "120")
      (footprint "eagle-import:R0805")
      (libsource (lib "eagle-import") (part "R-EU_R0805"))
    )
    (comp (ref "RJ_1")
      (value "RJ10")
      (footprint "eagle-import:RJ10")
      (libsource (lib "eagle-import") (part "RJ10"))
    )
    (comp (ref "RJ_2")
      (value "RJ10")
      (footprint "eagle-import:RJ10")
      (libsource (lib "eagle-import") (part "RJ10"))
    )
    (comp (ref "SJ1") (value "SJ") (footprint "eagle-import:SJ") (libsource (lib "eagle-import") (part "SJ")))
    (comp (ref "U$1")
      (value "MCP2551-I/SN")
      (footprint "eagle-import:SOIC127P600X175-8N")
      (libsource (lib "eagle-import") (part "MCP2551-I/SN"))
    )
    (comp (ref "U1")
      (value "TXB0108PWR")
      (footprint "eagle-import:SOP65P640X120-20N")
      (libsource (lib "eagle-import") (part "TXB0108PWR"))
    )
    (comp (ref "C33")
      (value "100n")
      (footprint "eagle-import:C0603")
      (libsource (lib "eagle-import") (part "C-EUC0603"))
    )
    (comp (ref "C34")
      (value "100n")
      (footprint "eagle-import:C0603")
      (libsource (lib "eagle-import") (part "C-EUC0603"))
    )
    (comp (ref "C36")
      (value "100n")
      (footprint "eagle-import:C0603")
      (libsource (lib "eagle-import") (part "C-EUC0603"))
    )
    (comp (ref "C37")
      (value "1µ/25V")
      (footprint "eagle-import:SMC_A")
      (libsource (lib "eagle-import") (part "CPOL-EUSMCA"))
    )
    (comp (ref "C39")
      (value "100n")
      (footprint "eagle-import:C0603")
      (libsource (lib "eagle-import") (part "C-EUC0603"))
    )
    (comp (ref "C41")
      (value "100n")
      (footprint "eagle-import:C0603")
      (libsource (lib "eagle-import") (part "C-EUC0603"))
    )
    (comp (ref "C44")
      (value "100n")
      (footprint "eagle-import:C0603")
      (libsource (lib "eagle-import") (part "C-EUC0603"))
    )
    (comp (ref "C45")
      (value "100n")
      (footprint "eagle-import:C0603")
      (libsource (lib "eagle-import") (part "C-EUC0603"))
    )
    (comp (ref "C47")
      (value "100n")
      (footprint "eagle-import:C0603")
      (libsource (lib "eagle-import") (part "C-EUC0603"))
    )
    (comp (ref "D14")
      (value "BZX84-A5V1")
      (footprint "eagle-import:TO236")
      (libsource (lib "eagle-import") (part "BZX84CSMD"))
    )
    (comp (ref "IC2")
      (value "4043D")
      (footprint "eagle-import:SO16")
      (libsource (lib "eagle-import") (part "4043D"))
    )
    (comp (ref "IC4")
      (value "LM1458D")
      (footprint "eagle-import:SO08")
      (libsource (lib "eagle-import") (part "1458DLM"))
    )
    (comp (ref "R5")
      (value "10k, 1%")
      (footprint "eagle-import:R0805")
      (libsource (lib "eagle-import") (part "R-EU_R0805"))
    )
    (comp (ref "R21")
      (value "33k, 1%")
      (footprint "eagle-import:R0805")
      (libsource (lib "eagle-import") (part "R-EU_R0805"))
    )
    (comp (ref "R22")
      (value "10k")
      (footprint "eagle-import:R0805")
      (libsource (lib "eagle-import") (part "R-EU_R0805"))
    )
    (comp (ref "R25")
      (value "100k")
      (footprint "eagle-import:R0805")
      (libsource (lib "eagle-import") (part "R-EU_R0805"))
    )
    (comp (ref "R26")
      (value "50k")
      (footprint "eagle-import:R0805")
      (libsource (lib "eagle-import") (part "R-EU_R0805"))
    )
    (comp (ref "R30")
      (value "3.3k")
      (footprint "eagle-import:R0805")
      (libsource (lib "eagle-import") (part "R-EU_R0805"))
    )
    (comp (ref "R52")
      (value "5,6k, 1%")
      (footprint "eagle-import:R0805")
      (libsource (lib "eagle-import") (part "R-EU_R0805"))
    )
    (comp (ref "R58")
      (value "10k")
      (footprint "eagle-import:R0805")
      (libsource (lib "eagle-import") (part "R-EU_R0805"))
    )
    (comp (ref "S1")
      (value "10-XX")
      (footprint "eagle-import:B3F-10XX")
      (libsource (lib "eagle-import") (part "10-XX"))
    )
    (comp (ref "T4")
      (value "BC849")
      (footprint "eagle-import:SOT23")
      (libsource (lib "eagle-import") (part "BC849"))
    )
    (comp (ref "U2")
      (value "SN74LVC2G02DCTR")
      (footprint "eagle-import:SOP65P400X130-8N")
      (libsource (lib "eagle-import") (part "SN74LVC2G02DCTR"))
    )
    (comp (ref "C1")
      (value "10µ/10V")
      (footprint "eagle-import:C0603")
      (libsource (lib "eagle-import") (part "C-EUC0603"))
    )
    (comp (ref "C2")
      (value "10µ/10V")
      (footprint "eagle-import:C0603")
      (libsource (lib "eagle-import") (part "C-EUC0603"))
    )
    (comp (ref "C3")
      (value "47µ/35V")
      (footprint "eagle-import:PANASONIC_D")
      (libsource (lib "eagle-import") (part "CPOL-EUD"))
    )
    (comp (ref "C17")
      (value "47µ/35V")
      (footprint "eagle-import:PANASONIC_D")
      (libsource (lib "eagle-import") (part "CPOL-EUD"))
    )
    (comp (ref "C18")
      (value "47µ/35V")
      (footprint "eagle-import:PANASONIC_D")
      (libsource (lib "eagle-import") (part "CPOL-EUD"))
    )
    (comp (ref "C19")
      (value "10n/35V")
      (footprint "eagle-import:C0603")
      (libsource (lib "eagle-import") (part "C-EUC0603"))
    )
    (comp (ref "C20")
      (value "47µ/35V")
      (footprint "eagle-import:PANASONIC_D")
      (libsource (lib "eagle-import") (part "CPOL-EUD"))
    )
    (comp (ref "C21")
      (value "47µ/35V")
      (footprint "eagle-import:PANASONIC_D")
      (libsource (lib "eagle-import") (part "CPOL-EUD"))
    )
    (comp (ref "C22")
      (value "10n/35V")
      (footprint "eagle-import:C0603")
      (libsource (lib "eagle-import") (part "C-EUC0603"))
    )
    (comp (ref "C40")
      (value "47µ/35V")
      (footprint "eagle-import:PANASONIC_D")
      (libsource (lib "eagle-import") (part "CPOL-EUD"))
    )
    (comp (ref "D1")
      (value "ES1A")
      (footprint "eagle-import:SMA-DO214AC")
      (libsource (lib "eagle-import") (part "GF1"))
    )
    (comp (ref "D2")
      (value "ES1A")
      (footprint "eagle-import:SMA-DO214AC")
      (libsource (lib "eagle-import") (part "GF1"))
    )
    (comp (ref "D6")
      (value "ES1A")
      (footprint "eagle-import:SMA-DO214AC")
      (libsource (lib "eagle-import") (part "GF1"))
    )
    (comp (ref "D7")
      (value "ES1A")
      (footprint "eagle-import:SMA-DO214AC")
      (libsource (lib "eagle-import") (part "GF1"))
    )
    (comp (ref "D15")
      (value "ES1A")
      (footprint "eagle-import:SMA-DO214AC")
      (libsource (lib "eagle-import") (part "GF1"))
    )
    (comp (ref "F1")
      (value "FUSETE5")
      (footprint "eagle-import:TE5")
      (libsource (lib "eagle-import") (part "FUSETE5"))
    )
    (comp (ref "H1")
      (value "MOUNT-PAD-ROUND3.0")
      (footprint "eagle-import:3,0-PAD")
      (libsource (lib "eagle-import") (part "MOUNT-PAD-ROUND3.0"))
    )
    (comp (ref "H2")
      (value "MOUNT-PAD-ROUND3.0")
      (footprint "eagle-import:3,0-PAD")
      (libsource (lib "eagle-import") (part "MOUNT-PAD-ROUND3.0"))
    )
    (comp (ref "H3")
      (value "MOUNT-PAD-ROUND3.0")
      (footprint "eagle-import:3,0-PAD")
      (libsource (lib "eagle-import") (part "MOUNT-PAD-ROUND3.0"))
    )
    (comp (ref "H4")
      (value "MOUNT-PAD-ROUND3.0")
      (footprint "eagle-import:3,0-PAD")
      (libsource (lib "eagle-import") (part "MOUNT-PAD-ROUND3.0"))
    )
    (comp (ref "IC3")
      (value "LM1117")
      (footprint "eagle-import:SOT223")
      (libsource (lib "eagle-import") (part "LM1117"))
    )
    (comp (ref "L1")
      (value "68µH")
      (footprint "eagle-import:PISM")
      (libsource (lib "eagle-import") (part "L-EUPISM"))
    )
    (comp (ref "L5")
      (value "100µH")
      (footprint "eagle-import:PISM")
      (libsource (lib "eagle-import") (part "L-EUPISM"))
    )
    (comp (ref "L6")
      (value "150µH")
      (footprint "eagle-import:PISM")
      (libsource (lib "eagle-import") (part "L-EUPISM"))
    )
    (comp (ref "LED4")
      (value "LEDCHIP-LED0805")
      (footprint "eagle-import:CHIP-LED0805")
      (libsource (lib "eagle-import") (part "LEDCHIP-LED0805"))
    )
    (comp (ref "LED5")
      (value "LEDCHIP-LED0805")
      (footprint "eagle-import:CHIP-LED0805")
      (libsource (lib "eagle-import") (part "LEDCHIP-LED0805"))
    )
    (comp (ref "LED6")
      (value "LEDCHIP-LED0805")
      (footprint "eagle-import:CHIP-LED0805")
      (libsource (lib "eagle-import") (part "LEDCHIP-LED0805"))
    )
    (comp (ref "LED7")
      (value "LEDCHIP-LED0805")
      (footprint "eagle-import:CHIP-LED0805")
      (libsource (lib "eagle-import") (part "LEDCHIP-LED0805"))
    )
    (comp (ref "LED10")
      (value "LEDCHIP-LED0805")
      (footprint "eagle-import:CHIP-LED0805")
      (libsource (lib "eagle-import") (part "LEDCHIP-LED0805"))
    )
    (comp (ref "R31")
      (value "50k")
      (footprint "eagle-import:R0805")
      (libsource (lib "eagle-import") (part "R-EU_R0805"))
    )
    (comp (ref "R42")
      (value "680")
      (footprint "eagle-import:R0805")
      (libsource (lib "eagle-import") (part "R-EU_R0805"))
    )
    (comp (ref "R43")
      (value "1,5k")
      (footprint "eagle-import:R0805")
      (libsource (lib "eagle-import") (part "R-EU_R0805"))
    )
    (comp (ref "R44")
      (value "4.7k")
      (footprint "eagle-import:R0805")
      (libsource (lib "eagle-import") (part "R-EU_R0805"))
    )
    (comp (ref "R45")
      (value "1,5k")
      (footprint "eagle-import:R0805")
      (libsource (lib "eagle-import") (part "R-EU_R0805"))
    )
    (comp (ref "R50")
      (value "5,6k")
      (footprint "eagle-import:R0805")
      (libsource (lib "eagle-import") (part "R-EU_R0805"))
    )
    (comp (ref "R59")
      (value "10k")
      (footprint "eagle-import:R0805")
      (libsource (lib "eagle-import") (part "R-EU_R0805"))
    )
    (comp (ref "U$8")
      (value "LM2576")
      (footprint "eagle-import:TO220511")
      (libsource (lib "eagle-import") (part "LM2576"))
    )
    (comp (ref "U3")
      (value "LM2675")
      (footprint "eagle-import:SOIC127P620X175-8N")
      (fields (field (name "MPN") "LM2675M-3.3"))
      (libsource (lib "eagle-import") (part "LM2675M-3.3"))
    )
    (comp (ref "U4")
      (value "LM2675")
      (footprint "eagle-import:SOIC127P620X175-8N")
      (fields (field (name "MPN") "LM2675M-3.3"))
      (libsource (lib "eagle-import") (part "LM2675M-3.3"))
    )
    (comp (ref "X1")
      (value "AK500/2-H")
      (footprint "eagle-import:AK500_2-H")
      (libsource (lib "eagle-import") (part "AK500/2-H"))
    )
    (comp (ref "C30")
      (value "47µ/35V")
      (footprint "eagle-import:E2-5")
      (libsource (lib "eagle-import") (part "CPOL-EUE2-5"))
    )
    (comp (ref "C31")
      (value "47µ/35V")
      (footprint "eagle-import:E2-5")
      (libsource (lib "eagle-import") (part "CPOL-EUE2-5"))
    )
    (comp (ref "COIL_IN")
      (value "WIREPADSMD5-5")
      (footprint "eagle-import:5-5")
      (libsource (lib "eagle-import") (part "WIREPADSMD5-5"))
    )
    (comp (ref "COIL_OUT")
      (value "WIREPADSMD5-5")
      (footprint "eagle-import:5-5")
      (libsource (lib "eagle-import") (part "WIREPADSMD5-5"))
    )
    (comp (ref "D5")
      (value "ES1A")
      (footprint "eagle-import:SMA-DO214AC")
      (libsource (lib "eagle-import") (part "GF1"))
    )
    (comp (ref "JP3")
      (value "PINHD-1X3")
      (footprint "eagle-import:1X03")
      (libsource (lib "eagle-import") (part "PINHD-1X3"))
    )
    (comp (ref "JP4")
      (value "PINHD-1X3")
      (footprint "eagle-import:1X03")
      (libsource (lib "eagle-import") (part "PINHD-1X3"))
    )
    (comp (ref "Q2")
      (value "IGW60T120")
      (footprint "eagle-import:TO247BV")
      (libsource (lib "eagle-import") (part "IRFPC40"))
    )
    (comp (ref "Q6")
      (value "IRF840")
      (footprint "eagle-import:TO220BV")
      (libsource (lib "eagle-import") (part "IRF740"))
    )
    (comp (ref "R2")
      (value "100")
      (footprint "eagle-import:HS25")
      (libsource (lib "eagle-import") (part "RHS25"))
    )
    (comp (ref "R3")
      (value "100")
      (footprint "eagle-import:HS25")
      (libsource (lib "eagle-import") (part "RHS25"))
    )
    (comp (ref "R12")
      (value "10k")
      (footprint "eagle-import:R0805")
      (libsource (lib "eagle-import") (part "R-EU_R0805"))
    )
    (comp (ref "R13")
      (value "5")
      (footprint "eagle-import:R2512")
      (libsource (lib "eagle-import") (part "R-EU_R2512"))
    )
    (comp (ref "R14")
      (value "390")
      (footprint "eagle-import:R0805")
      (libsource (lib "eagle-import") (part "R-EU_R0805"))
    )
    (comp (ref "R15")
      (value "10k")
      (footprint "eagle-import:R0805")
      (libsource (lib "eagle-import") (part "R-EU_R0805"))
    )
    (comp (ref "R16")
      (value "50k")
      (footprint "eagle-import:R0805")
      (libsource (lib "eagle-import") (part "R-EU_R0805"))
    )
    (comp (ref "R17")
      (value "390")
      (footprint "eagle-import:R0805")
      (libsource (lib "eagle-import") (part "R-EU_R0805"))
    )
    (comp (ref "R18")
      (value "5")
      (footprint "eagle-import:R2512")
      (libsource (lib "eagle-import") (part "R-EU_R2512"))
    )
    (comp (ref "R19")
      (value "5,6k")
      (footprint "eagle-import:R0805")
      (libsource (lib "eagle-import") (part "R-EU_R0805"))
    )
    (comp (ref "R20")
      (value "ERZE07A621")
      (footprint "eagle-import:S10K385")
      (libsource (lib "eagle-import") (part "S10K385"))
    )
    (comp (ref "R47")
      (value "5,6k")
      (footprint "eagle-import:R0805")
      (libsource (lib "eagle-import") (part "R-EU_R0805"))
    )
    (comp (ref "R51")
      (value "50k")
      (footprint "eagle-import:R0805")
      (libsource (lib "eagle-import") (part "R-EU_R0805"))
    )
    (comp (ref "R61")
      (value "5,6k")
      (footprint "eagle-import:R0805")
      (libsource (lib "eagle-import") (part "R-EU_R0805"))
    )
    (comp (ref "R70")
      (value "10k")
      (footprint "eagle-import:R0805")
      (libsource (lib "eagle-import") (part "R-EU_R0805"))
    )
    (comp (ref "T1")
      (value "BC849")
      (footprint "eagle-import:SOT23")
      (libsource (lib "eagle-import") (part "BC849"))
    )
    (comp (ref "T2")
      (value "BC849")
      (footprint "eagle-import:SOT23")
      (libsource (lib "eagle-import") (part "BC849"))
    )
    (comp (ref "T5")
      (value "IRLML6344TRPBF")
      (footprint "eagle-import:SOT-23")
      (libsource (lib "eagle-import") (part "NMOSSOT23"))
    )
    (comp (ref "T6")
      (value "BC859")
      (footprint "eagle-import:SOT23-BEC")
      (libsource (lib "eagle-import") (part "-PNP-SOT23-BECBC858C"))
    )
    (comp (ref "U$5")
      (value "SI8261ABC")
      (footprint "eagle-import:SOIC-8")
      (libsource (lib "eagle-import") (part "SI8261ABC"))
    )
    (comp (ref "U$6")
      (value "SI8261ABC")
      (footprint "eagle-import:SOIC-8")
      (libsource (lib "eagle-import") (part "SI8261ABC"))
    )
    (comp (ref "U$7")
      (value "DSEI30-12A")
      (footprint "eagle-import:TO247AD")
      (libsource (lib "eagle-import") (part "DSEI30-12A"))
    )
  )
  (nets
    (net (code "1") (name "+3V3") (class "Default")
      (node (ref "C2") (pin "1") (pinfunction "1_1") (pintype "passive"))
      (node (ref "C27") (pin "1") (pinfunction "1_1") (pintype "passive"))
      (node (ref "D2") (pin "A") (pinfunction "A_A") (pintype "passive"))
      (node (ref "IC3") (pin "2") (pinfunction "OUT_2") (pintype "passive"))
      (node (ref "IC3") (pin "4") (pinfunction "OUT_4") (pintype "input"))
      (node (ref "JP2") (pin "4") (pinfunction "4_4") (pintype "passive"))
      (node (ref "R42") (pin "2") (pinfunction "2_2") (pintype "passive"))
      (node (ref "U1") (pin "10") (pinfunction "OE_10") (pintype "input"))
      (node (ref "U1") (pin "2") (pinfunction "VCCA_2") (pintype "power_in"))
    )
    (net (code "2") (name "+5V") (class "Default")
      (node (ref "C1") (pin "1") (pinfunction "1_1") (pintype "passive"))
      (node (ref "C18") (pin "+") (pinfunction "+_+") (pintype "passive"))
      (node (ref "C26") (pin "1") (pinfunction "1_1") (pintype "passive"))
      (node (ref "C28") (pin "1") (pinfunction "1_1") (pintype "passive"))
      (node (ref "C34") (pin "1") (pinfunction "1_1") (pintype "passive"))
      (node (ref "C44") (pin "1") (pinfunction "1_1") (pintype "passive"))
      (node (ref "C45") (pin "1") (pinfunction "1_1") (pintype "passive"))
      (node (ref "C8") (pin "2") (pinfunction "2_2") (pintype "passive"))
      (node (ref "D2") (pin "K") (pinfunction "C_K") (pintype "passive"))
      (node (ref "IC2") (pin "16") (pinfunction "VDD_16") (pintype "power_in"))
      (node (ref "IC3") (pin "3") (pinfunction "IN_3") (pintype "input"))
      (node (ref "IC4") (pin "8") (pinfunction "V+_8") (pintype "power_in"))
      (node (ref "L5") (pin "1") (pinfunction "1_1") (pintype "passive"))
      (node (ref "OK2") (pin "8") (pinfunction "COL_8") (pintype "passive"))
      (node (ref "R17") (pin "2") (pinfunction "2_2") (pintype "passive"))
      (node (ref "R26") (pin "2") (pinfunction "2_2") (pintype "passive"))
      (node (ref "R43") (pin "2") (pinfunction "2_2") (pintype "passive"))
      (node (ref "R58") (pin "2") (pinfunction "2_2") (pintype "passive"))
      (node (ref "R70") (pin "1") (pinfunction "1_1") (pintype "passive"))
      (node (ref "S1") (pin "1") (pinfunction "S_1") (pintype "passive"))
      (node (ref "S1") (pin "2") (pinfunction "S1_2") (pintype "passive"))
      (node (ref "SV1") (pin "2") (pinfunction "2_2") (pintype "passive"))
      (node (ref "U$1") (pin "3") (pinfunction "VDD_3") (pintype "power_in"))
      (node (ref "U$2") (pin "4") (pinfunction "VCC_4") (pintype "bidirectional"))
      (node (ref "U1") (pin "19") (pinfunction "VCCB_19") (pintype "power_in"))
      (node (ref "U2") (pin "8") (pinfunction "VCC_8") (pintype "power_in"))
      (node (ref "U3") (pin "4") (pinfunction "FB_4") (pintype "input"))
    )
    (net (code "3") (name "+5V{slash}1") (class "Default")
      (node (ref "C40") (pin "+") (pinfunction "+_+") (pintype "passive"))
      (node (ref "JP3") (pin "2") (pinfunction "2_2") (pintype "passive"))
      (node (ref "JP4") (pin "2") (pinfunction "2_2") (pintype "passive"))
      (node (ref "L1") (pin "1") (pinfunction "1_1") (pintype "passive"))
      (node (ref "R45") (pin "2") (pinfunction "2_2") (pintype "passive"))
      (node (ref "U$8") (pin "4") (pinfunction "FB_4") (pintype "bidirectional"))
    )
    (net (code "4") (name "+5V{slash}3") (class "Default")
      (node (ref "C37") (pin "+") (pinfunction "+_+") (pintype "passive"))
      (node (ref "C39") (pin "1") (pinfunction "1_1") (pintype "passive"))
      (node (ref "C7") (pin "2") (pinfunction "2_2") (pintype "passive"))
      (node (ref "D14") (pin "C") (pinfunction "C_C") (pintype "passive"))
      (node (ref "OK1") (pin "6") (pinfunction "COL_6") (pintype "passive"))
      (node (ref "R30") (pin "1") (pinfunction "1_1") (pintype "passive"))
      (node (ref "R5") (pin "2") (pinfunction "2_2") (pintype "passive"))
      (node (ref "U$2") (pin "19") (pinfunction "AVCC_19") (pintype "bidirectional"))
    )
    (net (code "5") (name "+5V{slash}4") (class "Default")
      (node (ref "C16") (pin "1") (pinfunction "1_1") (pintype "passive"))
      (node (ref "C38") (pin "+") (pinfunction "+_+") (pintype "passive"))
      (node (ref "D12") (pin "C") (pinfunction "C_C") (pintype "passive"))
      (node (ref "OK1") (pin "8") (pinfunction "COL_8") (pintype "passive"))
      (node (ref "R29") (pin "1") (pinfunction "1_1") (pintype "passive"))
      (node (ref "R7") (pin "2") (pinfunction "2_2") (pintype "passive"))
    )
    (net (code "6") (name "+12V") (class "Default")
      (node (ref "C11") (pin "1") (pinfunction "1_1") (pintype "passive"))
      (node (ref "C21") (pin "+") (pinfunction "+_+") (pintype "passive"))
      (node (ref "L6") (pin "1") (pinfunction "1_1") (pintype "passive"))
      (node (ref "R44") (pin "2") (pinfunction "2_2") (pintype "passive"))
      (node (ref "U$3") (pin "12") (pinfunction "VCC_12") (pintype "bidirectional"))
      (node (ref "U4") (pin "4") (pinfunction "FB_4") (pintype "input"))
    )
    (net (code "7") (name "+24V") (class "Default")
      (node (ref "C17") (pin "+") (pinfunction "+_+") (pintype "passive"))
      (node (ref "C20") (pin "+") (pinfunction "+_+") (pintype "passive"))
      (node (ref "C3") (pin "+") (pinfunction "+_+") (pintype "passive"))
      (node (ref "C42") (pin "+") (pinfunction "+_+") (pintype "passive"))
      (node (ref "D1") (pin "K") (pinfunction "C_K") (pintype "passive"))
      (node (ref "F1") (pin "1") (pinfunction "1_1") (pintype "passive"))
      (node (ref "R30") (pin "2") (pinfunction "2_2") (pintype "passive"))
      (node (ref "R31") (pin "1") (pinfunction "1_1") (pintype "passive"))
      (node (ref "U$4") (pin "1") (pinfunction "U_IN_1") (pintype "bidirectional"))
      (node (ref "U$8") (pin "1") (pinfunction "VIN_1") (pintype "bidirectional"))
      (node (ref "U3") (pin "7") (pinfunction "VIN_7") (pintype "power_in"))
      (node (ref "U4") (pin "7") (pinfunction "VIN_7") (pintype "power_in"))
    )
    (net (code "8") (name "24V_PRI") (class "Default")
      (node (ref "C10") (pin "+") (pinfunction "+_+") (pintype "passive"))
      (node (ref "C35") (pin "1") (pinfunction "1_1") (pintype "passive"))
      (node (ref "C50") (pin "1") (pinfunction "1_1") (pintype "passive"))
      (node (ref "C9") (pin "+") (pinfunction "+_+") (pintype "passive"))
      (node (ref "Q3") (pin "D") (pinfunction "D_D") (pintype "passive"))
      (node (ref "Q5") (pin "4") (pinfunction "D_4") (pintype "passive"))
      (node (ref "R23") (pin "2") (pinfunction "2_2") (pintype "passive"))
      (node (ref "R27") (pin "2") (pinfunction "2_2") (pintype "passive"))
    )
    (net (code "9") (name "ACTIVATE_BOOSTER") (class "Default")
      (node (ref "R24") (pin "1") (pinfunction "1_1") (pintype "passive"))
      (node (ref "R25") (pin "1") (pinfunction "1_1") (pintype "passive"))
      (node (ref "U$2") (pin "26") (pinfunction "PB5_26") (pintype "bidirectional"))
    )
    (net (code "10") (name "ACTIVATE_SERVO") (class "Default")
      (node (ref "R47") (pin "1") (pinfunction "1_1") (pintype "passive"))
      (node (ref "U$2") (pin "15") (pinfunction "PD7_15") (pintype "bidirectional"))
    )
    (net (code "11") (name "ADC9{slash}FREI") (class "Default")
      (node (ref "U$2") (pin "18") (pinfunction "PC5_18") (pintype "bidirectional"))
    )
    (net (code "12") (name "ADC_24V_LOGIK{slash}SCK_A") (class "Default")
      (node (ref "R31") (pin "2") (pinfunction "2_2") (pintype "passive"))
      (node (ref "R50") (pin "1") (pinfunction "1_1") (pintype "passive"))
      (node (ref "SV1") (pin "7") (pinfunction "7_7") (pintype "passive"))
      (node (ref "U$2") (pin "12") (pinfunction "(RXD)PD4_12") (pintype "bidirectional"))
    )
    (net (code "13") (name "ADC_24V_PRI") (class "Default")
      (node (ref "R27") (pin "1") (pinfunction "1_1") (pintype "passive"))
      (node (ref "R28") (pin "2") (pinfunction "2_2") (pintype "passive"))
      (node (ref "U$2") (pin "13") (pinfunction "PD5_13") (pintype "bidirectional"))
    )
    (net (code "14") (name "ADC_CAP") (class "Default")
      (node (ref "C23") (pin "1") (pinfunction "1_1") (pintype "passive"))
      (node (ref "C47") (pin "1") (pinfunction "1_1") (pintype "passive"))
      (node (ref "IC4") (pin "3") (pinfunction "+IN_3") (pintype "input"))
      (node (ref "OK1") (pin "5") (pinfunction "EMIT_5") (pintype "passive"))
      (node (ref "R8") (pin "2") (pinfunction "2_2") (pintype "passive"))
      (node (ref "U$2") (pin "14") (pinfunction "PD6_14") (pintype "bidirectional"))
    )
    (net (code "15") (name "BOOSTER_24V") (class "Default")
      (node (ref "Q5") (pin "3") (pinfunction "S_3") (pintype "passive"))
      (node (ref "R200") (pin "2") (pinfunction "2_2") (pintype "passive"))
      (node (ref "R23") (pin "1") (pinfunction "1_1") (pintype "passive"))
      (node (ref "R46") (pin "2") (pinfunction "2_2") (pintype "passive"))
      (node (ref "X2") (pin "2") (pinfunction "KL_2") (pintype "passive"))
    )
    (net (code "16") (name "CAN_H") (class "Default")
      (node (ref "RJ_1") (pin "P$3") (pinfunction "P$3_P$3") (pintype "bidirectional"))
      (node (ref "RJ_2") (pin "P$3") (pinfunction "P$3_P$3") (pintype "bidirectional"))
      (node (ref "SJ1") (pin "2") (pinfunction "2_2") (pintype "passive"))
      (node (ref "U$1") (pin "7") (pinfunction "CANH_7") (pintype "bidirectional"))
    )
    (net (code "17") (name "CAN_L") (class "Default")
      (node (ref "R32") (pin "2") (pinfunction "2_2") (pintype "passive"))
      (node (ref "RJ_1") (pin "P$2") (pinfunction "P$2_P$2") (pintype "bidirectional"))
      (node (ref "RJ_2") (pin "P$2") (pinfunction "P$2_P$2") (pintype "bidirectional"))
      (node (ref "U$1") (pin "6") (pinfunction "CANL_6") (pintype "bidirectional"))
    )
    (net (code "18") (name "CAN_RX") (class "Default")
      (node (ref "U$1") (pin "4") (pinfunction "RXD_4") (pintype "output"))
      (node (ref "U$2") (pin "7") (pinfunction "(RXCAN)PC3_7") (pintype "bidirectional"))
    )
    (net (code "19") (name "CAN_TX") (class "Default")
      (node (ref "U$1") (pin "1") (pinfunction "TXD_1") (pintype "input"))
      (node (ref "U$2") (pin "6") (pinfunction "(TXCAN)PC2_6") (pintype "bidirectional"))
    )
    (net (code "20") (name "CAP_+12V") (class "Default")
      (node (ref "C29") (pin "+") (pinfunction "+_+") (pintype "passive"))
      (node (ref "C30") (pin "+") (pinfunction "+_+") (pintype "passive"))
      (node (ref "C31") (pin "+") (pinfunction "+_+") (pintype "passive"))
      (node (ref "C43") (pin "1") (pinfunction "1_1") (pintype "passive"))
      (node (ref "IC1") (pin "8") (pinfunction "V+_8") (pintype "power_in"))
      (node (ref "R29") (pin "2") (pinfunction "2_2") (pintype "passive"))
      (node (ref "R39") (pin "2") (pinfunction "2_2") (pintype "passive"))
      (node (ref "R40") (pin "2") (pinfunction "2_2") (pintype "passive"))
      (node (ref "R41") (pin "2") (pinfunction "2_2") (pintype "passive"))
      (node (ref "R49") (pin "2") (pinfunction "2_2") (pintype "passive"))
      (node (ref "T6") (pin "E") (pinfunction "E_E") (pintype "passive"))
      (node (ref "U$4") (pin "6") (pinfunction "+U_OUT_6") (pintype "bidirectional"))
      (node (ref "U$5") (pin "8") (pinfunction "VDD_8") (pintype "bidirectional"))
      (node (ref "U$6") (pin "8") (pinfunction "VDD_8") (pintype "bidirectional"))
    )
    (net (code "21") (name "CAP_0V") (class "Default")
      (node (ref "C14") (pin "2") (pinfunction "2_2") (pintype "passive"))
      (node (ref "C15") (pin "2") (pinfunction "2_2") (pintype "passive"))
      (node (ref "C16") (pin "2") (pinfunction "2_2") (pintype "passive"))
      (node (ref "C25") (pin "-") (pinfunction "-_-") (pintype "passive"))
      (node (ref "C29") (pin "-") (pinfunction "-_-") (pintype "passive"))
      (node (ref "C30") (pin "-") (pinfunction "-_-") (pintype "passive"))
      (node (ref "C31") (pin "-") (pinfunction "-_-") (pintype "passive"))
      (node (ref "C32") (pin "2") (pinfunction "2_2") (pintype "passive"))
      (node (ref "C38") (pin "-") (pinfunction "-_-") (pintype "passive"))
      (node (ref "C43") (pin "2") (pinfunction "2_2") (pintype "passive"))
      (node (ref "C46") (pin "2") (pinfunction "2_2") (pintype "passive"))
      (node (ref "C51") (pin "2") (pinfunction "2_2") (pintype "passive"))
      (node (ref "CAP_0V") (pin "P$1") (pinfunction "P_P$1") (pintype "passive"))
      (node (ref "D10") (pin "A") (pinfunction "A_A") (pintype "passive"))
      (node (ref "D11") (pin "A") (pinfunction "A_A") (pintype "passive"))
      (node (ref "D12") (pin "A") (pinfunction "A_A") (pintype "passive"))
      (node (ref "H1") (pin "B3,0") (pinfunction "MOUNT_B3,0") (pintype "passive"))
      (node (ref "IC1") (pin "4") (pinfunction "V-_4") (pintype "power_in"))
      (node (ref "LED9") (pin "C") (pinfunction "C_C") (pintype "passive"))
      (node (ref "OK1") (pin "4") (pinfunction "C_4") (pintype "passive"))
      (node (ref "OK2") (pin "2") (pinfunction "C_2") (pintype "passive"))
      (node (ref "Q2") (pin "S") (pinfunction "S_S") (pintype "passive"))
      (node (ref "Q6") (pin "S") (pinfunction "S_S") (pintype "passive"))
      (node (ref "R11") (pin "1") (pinfunction "1_1") (pintype "passive"))
      (node (ref "R12") (pin "1") (pinfunction "1_1") (pintype "passive"))
      (node (ref "R20") (pin "1") (pinfunction "1_1") (pintype "passive"))
      (node (ref "R36") (pin "1") (pinfunction "1_1") (pintype "passive"))
      (node (ref "R37") (pin "1") (pinfunction "1_1") (pintype "passive"))
      (node (ref "R38") (pin "1") (pinfunction "1_1") (pintype "passive"))
      (node (ref "R4") (pin "1") (pinfunction "1_1") (pintype "passive"))
      (node (ref "R6") (pin "1") (pinfunction "1_1") (pintype "passive"))
      (node (ref "U$4") (pin "4") (pinfunction "-U_OUT_4") (pintype "bidirectional"))
      (node (ref "U$5") (pin "5") (pinfunction "GND_5") (pintype "bidirectional"))
      (node (ref "U$6") (pin "5") (pinfunction "GND_5") (pintype "bidirectional"))
      (node (ref "VR1") (pin "3") (pinfunction "A_3") (pintype "passive"))
      (node (ref "VR2") (pin "3") (pinfunction "A_3") (pintype "passive"))
      (node (ref "VR3") (pin "3") (pinfunction "A_3") (pintype "passive"))
    )
    (net (code "22") (name "CAP_330V") (class "Default")
      (node (ref "C25") (pin "+") (pinfunction "+_+") (pintype "passive"))
      (node (ref "CAP_330V") (pin "P$1") (pinfunction "P_P$1") (pintype "passive"))
      (node (ref "COIL_OUT") (pin "P$1") (pinfunction "P_P$1") (pintype "passive"))
      (node (ref "D8") (pin "K") (pinfunction "C_K") (pintype "passive"))
      (node (ref "D9") (pin "K") (pinfunction "C_K") (pintype "passive"))
      (node (ref "R101") (pin "2") (pinfunction "2_2") (pintype "passive"))
      (node (ref "R2") (pin "1") (pinfunction "1_1") (pintype "passive"))
      (node (ref "R33") (pin "2") (pinfunction "2_2") (pintype "passive"))
      (node (ref "R34") (pin "2") (pinfunction "2_2") (pintype "passive"))
      (node (ref "R35") (pin "2") (pinfunction "2_2") (pintype "passive"))
      (node (ref "U$7") (pin "C") (pinfunction "C_C") (pintype "passive"))
    )
    (net (code "23") (name "CLKOUT_ETH") (class "Default")
      (node (ref "U1") (pin "12") (pinfunction "B8_12") (pintype "bidirectional"))
    )
    (net (code "24") (name "CLKOUT_ETH_3V") (class "Default")
      (node (ref "JP2") (pin "1") (pinfunction "1_1") (pintype "passive"))
      (node (ref "U1") (pin "9") (pinfunction "A8_9") (pintype "bidirectional"))
    )
    (net (code "25") (name "CS_ETH") (class "Default")
      (node (ref "U$2") (pin "29") (pinfunction "PD0_29") (pintype "bidirectional"))
      (node (ref "U1") (pin "13") (pinfunction "B7_13") (pintype "bidirectional"))
    )
    (net (code "26") (name "CS_ETH_3V") (class "Default")
      (node (ref "JP2") (pin "2") (pinfunction "2_2") (pintype "passive"))
      (node (ref "U1") (pin "8") (pinfunction "A7_8") (pintype "bidirectional"))
    )
    (net (code "27") (name "D2A") (class "Default")
      (node (ref "R52") (pin "1") (pinfunction "1_1") (pintype "passive"))
      (node (ref "U$2") (pin "25") (pinfunction "PC7_25") (pintype "bidirectional"))
    )
    (net (code "28") (name "FREI") (class "Default")
      (node (ref "U$2") (pin "16") (pinfunction "PB2_16") (pintype "bidirectional"))
    )
    (net (code "29") (name "FREI2") (class "Default")
      (node (ref "U$2") (pin "27") (pinfunction "PB6_27") (pintype "bidirectional"))
    )
    (net (code "30") (name "GND") (class "Default")
      (node (ref "C1") (pin "2") (pinfunction "2_2") (pintype "passive"))
      (node (ref "C11") (pin "2") (pinfunction "2_2") (pintype "passive"))
      (node (ref "C12") (pin "2") (pinfunction "2_2") (pintype "passive"))
      (node (ref "C17") (pin "-") (pinfunction "-_-") (pintype "passive"))
      (node (ref "C18") (pin "-") (pinfunction "-_-") (pintype "passive"))
      (node (ref "C2") (pin "2") (pinfunction "2_2") (pintype "passive"))
      (node (ref "C20") (pin "-") (pinfunction "-_-") (pintype "passive"))
      (node (ref "C21") (pin "-") (pinfunction "-_-") (pintype "passive"))
      (node (ref "C23") (pin "2") (pinfunction "2_2") (pintype "passive"))
      (node (ref "C24") (pin "2") (pinfunction "2_2") (pintype "passive"))
      (node (ref "C26") (pin "2") (pinfunction "2_2") (pintype "passive"))
      (node (ref "C27") (pin "2") (pinfunction "2_2") (pintype "passive"))
      (node (ref "C28") (pin "2") (pinfunction "2_2") (pintype "passive"))
      (node (ref "C3") (pin "-") (pinfunction "-_-") (pintype "passive"))
      (node (ref "C33") (pin "2") (pinfunction "2_2") (pintype "passive"))
      (node (ref "C34") (pin "2") (pinfunction "2_2") (pintype "passive"))
      (node (ref "C36") (pin "2") (pinfunction "2_2") (pintype "passive"))
      (node (ref "C37") (pin "-") (pinfunction "-_-") (pintype "passive"))
      (node (ref "C39") (pin "2") (pinfunction "2_2") (pintype "passive"))
      (node (ref "C4") (pin "1") (pinfunction "1_1") (pintype "passive"))
      (node (ref "C40") (pin "-") (pinfunction "-_-") (pintype "passive"))
      (node (ref "C41") (pin "2") (pinfunction "2_2") (pintype "passive"))
      (node (ref "C42") (pin "-") (pinfunction "-_-") (pintype "passive"))
      (node (ref "C44") (pin "2") (pinfunction "2_2") (pintype "passive"))
      (node (ref "C45") (pin "2") (pinfunction "2_2") (pintype "passive"))
      (node (ref "C47") (pin "2") (pinfunction "2_2") (pintype "passive"))
      (node (ref "C48") (pin "2") (pinfunction "2_2") (pintype "passive"))
      (node (ref "C49") (pin "2") (pinfunction "2_2") (pintype "passive"))
      (node (ref "C5") (pin "1") (pinfunction "1_1") (pintype "passive"))
      (node (ref "C6") (pin "1") (pinfunction "1_1") (pintype "passive"))
      (node (ref "C7") (pin "1") (pinfunction "1_1") (pintype "passive"))
      (node (ref "C8") (pin "1") (pinfunction "1_1") (pintype "passive"))
      (node (ref "CF") (pin "2") (pinfunction "2_2") (pintype "passive"))
      (node (ref "CSS") (pin "2") (pinfunction "2_2") (pintype "passive"))
      (node (ref "C_DELAY") (pin "2") (pinfunction "2_2") (pintype "passive"))
      (node (ref "C_ISEN_B") (pin "2") (pinfunction "2_2") (pintype "passive"))
      (node (ref "D1") (pin "A") (pinfunction "A_A") (pintype "passive"))
      (node (ref "D14") (pin "A") (pinfunction "A_A") (pintype "passive"))
      (node (ref "D15") (pin "A") (pinfunction "A_A") (pintype "passive"))
      (node (ref "D4") (pin "A") (pinfunction "A_A") (pintype "passive"))
      (node (ref "D6") (pin "A") (pinfunction "A_A") (pintype "passive"))
      (node (ref "D7") (pin "A") (pinfunction "A_A") (pintype "passive"))
      (node (ref "H2") (pin "B3,0") (pinfunction "MOUNT_B3,0") (pintype "passive"))
      (node (ref "H3") (pin "B3,0") (pinfunction "MOUNT_B3,0") (pintype "passive"))
      (node (ref "H4") (pin "B3,0") (pinfunction "MOUNT_B3,0") (pintype "passive"))
      (node (ref "IC2") (pin "3") (pinfunction "R0_3") (pintype "input"))
      (node (ref "IC2") (pin "4") (pinfunction "S0_4") (pintype "input"))
      (node (ref "IC2") (pin "6") (pinfunction "S1_6") (pintype "input"))
      (node (ref "IC2") (pin "7") (pinfunction "R1_7") (pintype "input"))
      (node (ref "IC2") (pin "8") (pinfunction "VSS_8") (pintype "power_in"))
      (node (ref "IC3") (pin "1") (pinfunction "GND_1") (pintype "input"))
      (node (ref "IC4") (pin "4") (pinfunction "V-_4") (pintype "power_in"))
      (node (ref "IC4") (pin "5") (pinfunction "+IN_5") (pintype "input"))
      (node (ref "IC4") (pin "6") (pinfunction "-IN_6") (pintype "input"))
      (node (ref "JP2") (pin "5") (pinfunction "5_5") (pintype "passive"))
      (node (ref "JP4") (pin "3") (pinfunction "3_3") (pintype "passive"))
      (node (ref "LED10") (pin "C") (pinfunction "C_C") (pintype "passive"))
      (node (ref "LED4") (pin "C") (pinfunction "C_C") (pintype "passive"))
      (node (ref "LED5") (pin "C") (pinfunction "C_C") (pintype "passive"))
      (node (ref "LED6") (pin "C") (pinfunction "C_C") (pintype "passive"))
      (node (ref "LED7") (pin "C") (pinfunction "C_C") (pintype "passive"))
      (node (ref "R1") (pin "1") (pinfunction "1_1") (pintype "passive"))
      (node (ref "R10") (pin "1") (pinfunction "1_1") (pintype "passive"))
      (node (ref "R16") (pin "1") (pinfunction "1_1") (pintype "passive"))
      (node (ref "R21") (pin "1") (pinfunction "1_1") (pintype "passive"))
      (node (ref "R22") (pin "1") (pinfunction "1_1") (pintype "passive"))
      (node (ref "R28") (pin "1") (pinfunction "1_1") (pintype "passive"))
      (node (ref "R50") (pin "2") (pinfunction "2_2") (pintype "passive"))
      (node (ref "R51") (pin "1") (pinfunction "1_1") (pintype "passive"))
      (node (ref "R8") (pin "1") (pinfunction "1_1") (pintype "passive"))
      (node (ref "RF_MIN") (pin "1") (pinfunction "1_1") (pintype "passive"))
      (node (ref "RJ_1") (pin "P$4") (pinfunction "P$4_P$4") (pintype "bidirectional"))
      (node (ref "RJ_2") (pin "P$4") (pinfunction "P$4_P$4") (pintype "bidirectional"))
      (node (ref "R_DELAY") (pin "1") (pinfunction "1_1") (pintype "passive"))
      (node (ref "R_ISEN_B") (pin "1") (pinfunction "1_1") (pintype "passive"))
      (node (ref "SV1") (pin "10") (pinfunction "10_10") (pintype "passive"))
      (node (ref "SV1") (pin "4") (pinfunction "4_4") (pintype "passive"))
      (node (ref "SV1") (pin "6") (pinfunction "6_6") (pintype "passive"))
      (node (ref "SV1") (pin "8") (pinfunction "8_8") (pintype "passive"))
      (node (ref "T1") (pin "2") (pinfunction "E_2") (pintype "passive"))
      (node (ref "T2") (pin "2") (pinfunction "E_2") (pintype "passive"))
      (node (ref "T4") (pin "2") (pinfunction "E_2") (pintype "passive"))
      (node (ref "T5") (pin "2") (pinfunction "S_2") (pintype "passive"))
      (node (ref "T8") (pin "2") (pinfunction "E_2") (pintype "passive"))
      (node (ref "U$1") (pin "2") (pinfunction "VSS_2") (pintype "passive"))
      (node (ref "U$2") (pin "20") (pinfunction "AGND_20") (pintype "power_in"))
      (node (ref "U$2") (pin "5") (pinfunction "GND_5") (pintype "power_in"))
      (node (ref "U$3") (pin "10") (pinfunction "GND_10") (pintype "bidirectional"))
      (node (ref "U$3") (pin "8") (pinfunction "DIS_8") (pintype "bidirectional"))
      (node (ref "U$4") (pin "2") (pinfunction "GND_2") (pintype "bidirectional"))
      (node (ref "U$5") (pin "1") (pinfunction "NC_1") (pintype "bidirectional"))
      (node (ref "U$5") (pin "3") (pinfunction "CATHODE_3") (pintype "bidirectional"))
      (node (ref "U$5") (pin "4") (pinfunction "NC_4") (pintype "bidirectional"))
      (node (ref "U$6") (pin "1") (pinfunction "NC_1") (pintype "bidirectional"))
      (node (ref "U$6") (pin "4") (pinfunction "NC_4") (pintype "bidirectional"))
      (node (ref "U$8") (pin "3") (pinfunction "GND_3") (pintype "bidirectional"))
      (node (ref "U$8") (pin "5") (pinfunction "~{ON}/OFF_5") (pintype "bidirectional"))
      (node (ref "U1") (pin "11") (pinfunction "GND_11") (pintype "passive"))
      (node (ref "U2") (pin "4") (pinfunction "GND_4") (pintype "passive"))
      (node (ref "U3") (pin "6") (pinfunction "GND_6") (pintype "passive"))
      (node (ref "U4") (pin "6") (pinfunction "GND_6") (pintype "passive"))
      (node (ref "X1") (pin "2") (pinfunction "KL_2") (pintype "passive"))
    )
    (net (code "31") (name "GND1") (class "Default")
      (node (ref "C10") (pin "-") (pinfunction "-_-") (pintype "passive"))
      (node (ref "C13") (pin "2") (pinfunction "2_2") (pintype "passive"))
      (node (ref "C35") (pin "2") (pinfunction "2_2") (pintype "passive"))
      (node (ref "C50") (pin "2") (pinfunction "2_2") (pintype "passive"))
      (node (ref "C9") (pin "-") (pinfunction "-_-") (pintype "passive"))
      (node (ref "LED8") (pin "C") (pinfunction "C_C") (pintype "passive"))
      (node (ref "Q4") (pin "S") (pinfunction "S_S") (pintype "passive"))
      (node (ref "R54") (pin "2") (pinfunction "2_2") (pintype "passive"))
      (node (ref "T3") (pin "2") (pinfunction "E_2") (pintype "passive"))
      (node (ref "X2") (pin "1") (pinfunction "KL_1") (pintype "passive"))
    )
    (net (code "32") (name "INT_ETH") (class "Default")
      (node (ref "U$2") (pin "30") (pinfunction "PC0_30") (pintype "bidirectional"))
      (node (ref "U1") (pin "20") (pinfunction "B1_20") (pintype "bidirectional"))
    )
    (net (code "33") (name "INT_ETH_3V") (class "Default")
      (node (ref "JP1") (pin "5") (pinfunction "5_5") (pintype "passive"))
      (node (ref "U1") (pin "1") (pinfunction "A1_1") (pintype "bidirectional"))
    )
    (net (code "34") (name "KICK") (class "Default")
      (node (ref "R19") (pin "1") (pinfunction "1_1") (pintype "passive"))
      (node (ref "U$2") (pin "23") (pinfunction "PB3_23") (pintype "bidirectional"))
    )
    (net (code "35") (name "LINE") (class "Default")
      (node (ref "C48") (pin "1") (pinfunction "1_1") (pintype "passive"))
      (node (ref "R70") (pin "2") (pinfunction "2_2") (pintype "passive"))
      (node (ref "T1") (pin "3") (pinfunction "C_3") (pintype "passive"))
      (node (ref "T2") (pin "3") (pinfunction "C_3") (pintype "passive"))
      (node (ref "U$3") (pin "7") (pinfunction "LINE_7") (pintype "bidirectional"))
      (node (ref "U$6") (pin "3") (pinfunction "CATHODE_3") (pintype "bidirectional"))
    )
    (net (code "36") (name "MISO") (class "Default")
      (node (ref "U$2") (pin "8") (pinfunction "PB0_8") (pintype "bidirectional"))
      (node (ref "U1") (pin "17") (pinfunction "B3_17") (pintype "bidirectional"))
    )
    (net (code "37") (name "MISO_3V") (class "Default")
      (node (ref "JP1") (pin "3") (pinfunction "3_3") (pintype "passive"))
      (node (ref "U1") (pin "4") (pinfunction "A3_4") (pintype "bidirectional"))
    )
    (net (code "38") (name "MOSI") (class "Default")
      (node (ref "U$2") (pin "9") (pinfunction "PB1_9") (pintype "bidirectional"))
      (node (ref "U1") (pin "16") (pinfunction "B4_16") (pintype "bidirectional"))
    )
    (net (code "39") (name "MOSI_3V") (class "Default")
      (node (ref "JP1") (pin "2") (pinfunction "2_2") (pintype "passive"))
      (node (ref "U1") (pin "5") (pinfunction "A4_5") (pintype "bidirectional"))
    )
    (net (code "40") (name "NOTAUS") (class "Default")
      (node (ref "R14") (pin "1") (pinfunction "1_1") (pintype "passive"))
      (node (ref "R55") (pin "2") (pinfunction "2_2") (pintype "passive"))
      (node (ref "R61") (pin "1") (pinfunction "1_1") (pintype "passive"))
      (node (ref "U2") (pin "7") (pinfunction "1Y_7") (pintype "output"))
    )
    (net (code "41") (name "Net-(COIL_IN-P)") (class "Default")
      (node (ref "COIL_IN") (pin "P$1") (pinfunction "P_P$1") (pintype "passive"))
      (node (ref "Q2") (pin "D") (pinfunction "D_D") (pintype "passive"))
      (node (ref "R20") (pin "2") (pinfunction "2_2") (pintype "passive"))
      (node (ref "U$7") (pin "A") (pinfunction "A_A") (pintype "passive"))
    )
    (net (code "42") (name "Net-(C_ISEN_A-Pad1)") (class "Default")
      (node (ref "C_ISEN_A") (pin "1") (pinfunction "1_1") (pintype "passive"))
      (node (ref "R_ISEN_A") (pin "2") (pinfunction "2_2") (pintype "passive"))
    )
    (net (code "43") (name "Net-(D3-PadA)") (class "Default")
      (node (ref "D3") (pin "A") (pinfunction "A_A") (pintype "passive"))
      (node (ref "D4") (pin "C") (pinfunction "C_C") (pintype "passive"))
      (node (ref "R_ISEN_A") (pin "1") (pinfunction "1_1") (pintype "passive"))
    )
    (net (code "44") (name "Net-(D5-C)") (class "Default")
      (node (ref "D5") (pin "K") (pinfunction "C_K") (pintype "passive"))
      (node (ref "R18") (pin "1") (pinfunction "1_1") (pintype "passive"))
      (node (ref "U$6") (pin "6") (pinfunction "VO_6") (pintype "bidirectional"))
      (node (ref "U$6") (pin "7") (pinfunction "VO_7") (pintype "bidirectional"))
    )
    (net (code "45") (name "Net-(D5-PadA)") (class "Default")
      (node (ref "D5") (pin "A") (pinfunction "A_A") (pintype "passive"))
      (node (ref "R13") (pin "1") (pinfunction "1_1") (pintype "passive"))
    )
    (net (code "46") (name "Net-(D6-C)") (class "Default")
      (node (ref "C19") (pin "2") (pinfunction "2_2") (pintype "passive"))
      (node (ref "D6") (pin "K") (pinfunction "C_K") (pintype "passive"))
      (node (ref "L5") (pin "2") (pinfunction "2_2") (pintype "passive"))
      (node (ref "U3") (pin "8") (pinfunction "VSW_8") (pintype "output"))
    )
    (net (code "47") (name "Net-(D7-C)") (class "Default")
      (node (ref "C22") (pin "2") (pinfunction "2_2") (pintype "passive"))
      (node (ref "D7") (pin "K") (pinfunction "C_K") (pintype "passive"))
      (node (ref "L6") (pin "2") (pinfunction "2_2") (pintype "passive"))
      (node (ref "U4") (pin "8") (pinfunction "VSW_8") (pintype "output"))
    )
    (net (code "48") (name "Net-(D10-C)") (class "Default")
      (node (ref "D10") (pin "K") (pinfunction "C_K") (pintype "passive"))
      (node (ref "D8") (pin "A") (pinfunction "A_A") (pintype "passive"))
      (node (ref "L7") (pin "2") (pinfunction "8_2") (pintype "passive"))
    )
    (net (code "49") (name "Net-(D11-C)") (class "Default")
      (node (ref "D11") (pin "K") (pinfunction "C_K") (pintype "passive"))
      (node (ref "D9") (pin "A") (pinfunction "A_A") (pintype "passive"))
      (node (ref "L7") (pin "4") (pinfunction "1_4") (pintype "passive"))
    )
    (net (code "50") (name "Net-(D15-C)") (class "Default")
      (node (ref "D15") (pin "K") (pinfunction "C_K") (pintype "passive"))
      (node (ref "L1") (pin "2") (pinfunction "2_2") (pintype "passive"))
      (node (ref "U$8") (pin "2") (pinfunction "VOUT_2") (pintype "bidirectional"))
    )
    (net (code "51") (name "Net-(IC1A-+IN)") (class "Default")
      (node (ref "C15") (pin "1") (pinfunction "1_1") (pintype "passive"))
      (node (ref "C32") (pin "1") (pinfunction "1_1") (pintype "passive"))
      (node (ref "IC1") (pin "3") (pinfunction "+IN_3") (pintype "input"))
      (node (ref "IC1") (pin "5") (pinfunction "+IN_5") (pintype "input"))
      (node (ref "R101") (pin "1") (pinfunction "1_1") (pintype "passive"))
      (node (ref "R6") (pin "2") (pinfunction "2_2") (pintype "passive"))
    )
    (net (code "52") (name "Net-(IC1A--IN)") (class "Default")
      (node (ref "C14") (pin "1") (pinfunction "1_1") (pintype "passive"))
      (node (ref "C51") (pin "1") (pinfunction "1_1") (pintype "passive"))
      (node (ref "IC1") (pin "2") (pinfunction "-IN_2") (pintype "input"))
      (node (ref "OK1") (pin "7") (pinfunction "EMIT_7") (pintype "passive"))
      (node (ref "R11") (pin "2") (pinfunction "2_2") (pintype "passive"))
    )
    (net (code "53") (name "Net-(IC1A-OUT)") (class "Default")
      (node (ref "IC1") (pin "1") (pinfunction "OUT_1") (pintype "output"))
      (node (ref "R105") (pin "1") (pinfunction "1_1") (pintype "passive"))
    )
    (net (code "54") (name "Net-(IC1B--IN)") (class "Default")
      (node (ref "C46") (pin "1") (pinfunction "1_1") (pintype "passive"))
      (node (ref "IC1") (pin "6") (pinfunction "-IN_6") (pintype "input"))
      (node (ref "R4") (pin "2") (pinfunction "2_2") (pintype "passive"))
      (node (ref "R7") (pin "1") (pinfunction "1_1") (pintype "passive"))
    )
    (net (code "55") (name "Net-(IC1B-OUT)") (class "Default")
      (node (ref "IC1") (pin "7") (pinfunction "OUT_7") (pintype "output"))
      (node (ref "R9") (pin "1") (pinfunction "1_1") (pintype "passive"))
    )
    (net (code "56") (name "Net-(IC2A-EN)") (class "Default")
      (node (ref "IC2") (pin "5") (pinfunction "EN_5") (pintype "input"))
      (node (ref "R58") (pin "1") (pinfunction "1_1") (pintype "passive"))
    )
    (net (code "57") (name "Net-(IC2A-Q2)") (class "Default")
      (node (ref "IC2") (pin "10") (pinfunction "Q2_10") (pintype "output"))
      (node (ref "U2") (pin "1") (pinfunction "1A_1") (pintype "input"))
    )
    (net (code "58") (name "Net-(IC2A-Q3)") (class "Default")
      (node (ref "IC2") (pin "1") (pinfunction "Q3_1") (pintype "output"))
      (node (ref "U2") (pin "5") (pinfunction "2A_5") (pintype "input"))
    )
    (net (code "59") (name "Net-(IC4A--IN)") (class "Default")
      (node (ref "C36") (pin "1") (pinfunction "1_1") (pintype "passive"))
      (node (ref "IC4") (pin "2") (pinfunction "-IN_2") (pintype "input"))
      (node (ref "R21") (pin "2") (pinfunction "2_2") (pintype "passive"))
      (node (ref "R5") (pin "1") (pinfunction "1_1") (pintype "passive"))
      (node (ref "R52") (pin "2") (pinfunction "2_2") (pintype "passive"))
    )
    (net (code "60") (name "Net-(IC4A-OUT)") (class "Default")
      (node (ref "IC4") (pin "1") (pinfunction "OUT_1") (pintype "output"))
      (node (ref "U2") (pin "6") (pinfunction "2B_6") (pintype "input"))
    )
    (net (code "61") (name "Net-(L7-4)") (class "Default")
      (node (ref "L3") (pin "1") (pinfunction "1_1") (pintype "passive"))
      (node (ref "L4") (pin "1") (pinfunction "1_1") (pintype "passive"))
      (node (ref "L7") (pin "9") (pinfunction "4_9") (pintype "passive"))
    )
    (net (code "62") (name "Net-(L7-5)") (class "Default")
      (node (ref "C13") (pin "1") (pinfunction "1_1") (pintype "passive"))
      (node (ref "C_ISEN_A") (pin "2") (pinfunction "2_2") (pintype "passive"))
      (node (ref "L3") (pin "2") (pinfunction "2_2") (pintype "passive"))
      (node (ref "L7") (pin "11") (pinfunction "5_11") (pintype "passive"))
    )
    (net (code "63") (name "Net-(LED1-PadA)") (class "Default")
      (node (ref "LED1") (pin "A") (pinfunction "A_A") (pintype "passive"))
      (node (ref "R39") (pin "1") (pinfunction "1_1") (pintype "passive"))
    )
    (net (code "64") (name "Net-(LED2-PadA)") (class "Default")
      (node (ref "LED2") (pin "A") (pinfunction "A_A") (pintype "passive"))
      (node (ref "R40") (pin "1") (pinfunction "1_1") (pintype "passive"))
    )
    (net (code "65") (name "Net-(LED3-PadA)") (class "Default")
      (node (ref "LED3") (pin "A") (pinfunction "A_A") (pintype "passive"))
      (node (ref "R41") (pin "1") (pinfunction "1_1") (pintype "passive"))
    )
    (net (code "66") (name "Net-(LED4-PadA)") (class "Default")
      (node (ref "LED4") (pin "A") (pinfunction "A_A") (pintype "passive"))
      (node (ref "R42") (pin "1") (pinfunction "1_1") (pintype "passive"))
    )
    (net (code "67") (name "Net-(LED5-PadA)") (class "Default")
      (node (ref "LED5") (pin "A") (pinfunction "A_A") (pintype "passive"))
      (node (ref "R43") (pin "1") (pinfunction "1_1") (pintype "passive"))
    )
    (net (code "68") (name "Net-(LED6-PadA)") (class "Default")
      (node (ref "LED6") (pin "A") (pinfunction "A_A") (pintype "passive"))
      (node (ref "R44") (pin "1") (pinfunction "1_1") (pintype "passive"))
    )
    (net (code "69") (name "Net-(LED7-PadA)") (class "Default")
      (node (ref "LED7") (pin "A") (pinfunction "A_A") (pintype "passive"))
      (node (ref "R45") (pin "1") (pinfunction "1_1") (pintype "passive"))
    )
    (net (code "70") (name "Net-(LED8-PadA)") (class "Default")
      (node (ref "LED8") (pin "A") (pinfunction "A_A") (pintype "passive"))
      (node (ref "R46") (pin "1") (pinfunction "1_1") (pintype "passive"))
    )
    (net (code "71") (name "Net-(LED9-PadA)") (class "Default")
      (node (ref "LED9") (pin "A") (pinfunction "A_A") (pintype "passive"))
      (node (ref "R49") (pin "1") (pinfunction "1_1") (pintype "passive"))
    )
    (net (code "72") (name "Net-(LED10-PadA)") (class "Default")
      (node (ref "LED10") (pin "A") (pinfunction "A_A") (pintype "passive"))
      (node (ref "R59") (pin "1") (pinfunction "1_1") (pintype "passive"))
    )
    (net (code "73") (name "Net-(OK1A-A)") (class "Default")
      (node (ref "OK1") (pin "1") (pinfunction "A_1") (pintype "passive"))
      (node (ref "R105") (pin "2") (pinfunction "2_2") (pintype "passive"))
    )
    (net (code "74") (name "Net-(OK1A-C)") (class "Default")
      (node (ref "OK1") (pin "2") (pinfunction "C_2") (pintype "passive"))
      (node (ref "OK1") (pin "3") (pinfunction "A_3") (pintype "passive"))
    )
    (net (code "75") (name "Net-(OK2A-A)") (class "Default")
      (node (ref "OK2") (pin "1") (pinfunction "A_1") (pintype "passive"))
      (node (ref "R9") (pin "2") (pinfunction "2_2") (pintype "passive"))
    )
    (net (code "76") (name "Net-(Q2-PadG)") (class "Default")
      (node (ref "Q2") (pin "G") (pinfunction "G_G") (pintype "passive"))
      (node (ref "R13") (pin "2") (pinfunction "2_2") (pintype "passive"))
      (node (ref "R18") (pin "2") (pinfunction "2_2") (pintype "passive"))
    )
    (net (code "77") (name "Net-(Q5-G)") (class "Default")
      (node (ref "D13") (pin "C") (pinfunction "C_C") (pintype "passive"))
      (node (ref "Q5") (pin "1") (pinfunction "G_1") (pintype "passive"))
      (node (ref "R200") (pin "1") (pinfunction "1_1") (pintype "passive"))
    )
    (net (code "78") (name "Net-(Q6-PadD)") (class "Default")
      (node (ref "Q6") (pin "D") (pinfunction "D_D") (pintype "passive"))
      (node (ref "R3") (pin "2") (pinfunction "2_2") (pintype "passive"))
    )
    (net (code "79") (name "Net-(Q6-PadG)") (class "Default")
      (node (ref "Q6") (pin "G") (pinfunction "G_G") (pintype "passive"))
      (node (ref "R12") (pin "2") (pinfunction "2_2") (pintype "passive"))
      (node (ref "T6") (pin "C") (pinfunction "C_C") (pintype "passive"))
    )
    (net (code "80") (name "Net-(R2-Pad2)") (class "Default")
      (node (ref "R2") (pin "2") (pinfunction "2_2") (pintype "passive"))
      (node (ref "R3") (pin "1") (pinfunction "1_1") (pintype "passive"))
    )
    (net (code "81") (name "Net-(R15-Pad1)") (class "Default")
      (node (ref "R15") (pin "1") (pinfunction "1_1") (pintype "passive"))
      (node (ref "U$5") (pin "6") (pinfunction "VO_6") (pintype "bidirectional"))
      (node (ref "U$5") (pin "7") (pinfunction "VO_7") (pintype "bidirectional"))
    )
    (net (code "82") (name "Net-(R15-Pad2)") (class "Default")
      (node (ref "R15") (pin "2") (pinfunction "2_2") (pintype "passive"))
      (node (ref "T6") (pin "B") (pinfunction "B_B") (pintype "passive"))
    )
    (net (code "83") (name "Net-(R32-Pad1)") (class "Default")
      (node (ref "R32") (pin "1") (pinfunction "1_1") (pintype "passive"))
      (node (ref "SJ1") (pin "1") (pinfunction "1_1") (pintype "passive"))
    )
    (net (code "84") (name "Net-(T1-B)") (class "Default")
      (node (ref "R61") (pin "2") (pinfunction "2_2") (pintype "passive"))
      (node (ref "T1") (pin "1") (pinfunction "B_1") (pintype "passive"))
    )
    (net (code "85") (name "Net-(T2-B)") (class "Default")
      (node (ref "R19") (pin "2") (pinfunction "2_2") (pintype "passive"))
      (node (ref "R51") (pin "2") (pinfunction "2_2") (pintype "passive"))
      (node (ref "T2") (pin "1") (pinfunction "B_1") (pintype "passive"))
    )
    (net (code "86") (name "Net-(T3-B)") (class "Default")
      (node (ref "R24") (pin "2") (pinfunction "2_2") (pintype "passive"))
      (node (ref "T3") (pin "1") (pinfunction "B_1") (pintype "passive"))
    )
    (net (code "87") (name "Net-(T3-C)") (class "Default")
      (node (ref "D13") (pin "A") (pinfunction "A_A") (pintype "passive"))
      (node (ref "T3") (pin "3") (pinfunction "C_3") (pintype "passive"))
    )
    (net (code "88") (name "Net-(T4-B)") (class "Default")
      (node (ref "R25") (pin "2") (pinfunction "2_2") (pintype "passive"))
      (node (ref "T4") (pin "1") (pinfunction "B_1") (pintype "passive"))
    )
    (net (code "89") (name "Net-(T4-C)") (class "Default")
      (node (ref "R26") (pin "1") (pinfunction "1_1") (pintype "passive"))
      (node (ref "T4") (pin "3") (pinfunction "C_3") (pintype "passive"))
      (node (ref "U2") (pin "2") (pinfunction "1B_2") (pintype "input"))
    )
    (net (code "90") (name "Net-(T5-D)") (class "Default")
      (node (ref "JP3") (pin "3") (pinfunction "3_3") (pintype "passive"))
      (node (ref "T5") (pin "1") (pinfunction "D_1") (pintype "passive"))
    )
    (net (code "91") (name "Net-(T5-G)") (class "Default")
      (node (ref "R16") (pin "2") (pinfunction "2_2") (pintype "passive"))
      (node (ref "R47") (pin "2") (pinfunction "2_2") (pintype "passive"))
      (node (ref "T5") (pin "3") (pinfunction "G_3") (pintype "passive"))
    )
    (net (code "92") (name "Net-(T8-B)") (class "Default")
      (node (ref "C49") (pin "1") (pinfunction "1_1") (pintype "passive"))
      (node (ref "R48") (pin "2") (pinfunction "2_2") (pintype "passive"))
      (node (ref "T8") (pin "1") (pinfunction "B_1") (pintype "passive"))
    )
    (net (code "93") (name "Net-(T8-C)") (class "Default")
      (node (ref "RF_MAX") (pin "1") (pinfunction "1_1") (pintype "passive"))
      (node (ref "T8") (pin "3") (pinfunction "C_3") (pintype "passive"))
    )
    (net (code "94") (name "Net-(U$1-RS)") (class "Default")
      (node (ref "R1") (pin "2") (pinfunction "2_2") (pintype "passive"))
      (node (ref "U$1") (pin "8") (pinfunction "RS_8") (pintype "input"))
    )
    (net (code "95") (name "Net-(U$2-AREF)") (class "Default")
      (node (ref "C6") (pin "2") (pinfunction "2_2") (pintype "passive"))
      (node (ref "U$2") (pin "21") (pinfunction "AREF_21") (pintype "bidirectional"))
    )
    (net (code "96") (name "Net-(U$2-PC4)") (class "Default")
      (node (ref "R57") (pin "1") (pinfunction "1_1") (pintype "passive"))
      (node (ref "U$2") (pin "17") (pinfunction "PC4_17") (pintype "bidirectional"))
    )
    (net (code "97") (name "Net-(U$2-PC6)") (class "Default")
      (node (ref "R55") (pin "1") (pinfunction "1_1") (pintype "passive"))
      (node (ref "U$2") (pin "22") (pinfunction "PC6_22") (pintype "bidirectional"))
    )
    (net (code "98") (name "Net-(U$2-PE1(XTAL1))") (class "Default")
      (node (ref "C5") (pin "2") (pinfunction "2_2") (pintype "passive"))
      (node (ref "Q1") (pin "1") (pinfunction "1_1") (pintype "passive"))
      (node (ref "U$2") (pin "10") (pinfunction "PE1(XTAL1)_10") (pintype "bidirectional"))
    )
    (net (code "99") (name "Net-(U$2-PE2(XTAL2))") (class "Default")
      (node (ref "C4") (pin "2") (pinfunction "2_2") (pintype "passive"))
      (node (ref "Q1") (pin "2") (pinfunction "2_2") (pintype "passive"))
      (node (ref "U$2") (pin "11") (pinfunction "PE2(XTAL2)_11") (pintype "bidirectional"))
    )
    (net (code "100") (name "Net-(U$3-CF)") (class "Default")
      (node (ref "CF") (pin "1") (pinfunction "1_1") (pintype "passive"))
      (node (ref "U$3") (pin "3") (pinfunction "CF_3") (pintype "bidirectional"))
    )
    (net (code "101") (name "Net-(U$3-CSS)") (class "Default")
      (node (ref "CSS") (pin "1") (pinfunction "1_1") (pintype "passive"))
      (node (ref "R_SS") (pin "1") (pinfunction "1_1") (pintype "passive"))
      (node (ref "U$3") (pin "1") (pinfunction "CSS_1") (pintype "bidirectional"))
    )
    (net (code "102") (name "Net-(U$3-DELAY)") (class "Default")
      (node (ref "C_DELAY") (pin "1") (pinfunction "1_1") (pintype "passive"))
      (node (ref "R_DELAY") (pin "2") (pinfunction "2_2") (pintype "passive"))
      (node (ref "U$3") (pin "2") (pinfunction "DELAY_2") (pintype "bidirectional"))
    )
    (net (code "103") (name "Net-(U$3-HVG)") (class "Default")
      (node (ref "Q3") (pin "G") (pinfunction "G_G") (pintype "passive"))
      (node (ref "R53") (pin "1") (pinfunction "1_1") (pintype "passive"))
      (node (ref "U$3") (pin "15") (pinfunction "HVG_15") (pintype "bidirectional"))
    )
    (net (code "104") (name "Net-(U$3-ISEN)") (class "Default")
      (node (ref "C_ISEN_B") (pin "1") (pinfunction "1_1") (pintype "passive"))
      (node (ref "D3") (pin "C") (pinfunction "C_C") (pintype "passive"))
      (node (ref "R_ISEN_B") (pin "2") (pinfunction "2_2") (pintype "passive"))
      (node (ref "U$3") (pin "6") (pinfunction "ISEN_6") (pintype "bidirectional"))
    )
    (net (code "105") (name "Net-(U$3-LVG)") (class "Default")
      (node (ref "Q4") (pin "G") (pinfunction "G_G") (pintype "passive"))
      (node (ref "R54") (pin "1") (pinfunction "1_1") (pintype "passive"))
      (node (ref "U$3") (pin "11") (pinfunction "LVG_11") (pintype "bidirectional"))
    )
    (net (code "106") (name "Net-(U$3-OUT)") (class "Default")
      (node (ref "C_BOOT") (pin "2") (pinfunction "2_2") (pintype "passive"))
      (node (ref "L4") (pin "2") (pinfunction "2_2") (pintype "passive"))
      (node (ref "Q3") (pin "S") (pinfunction "S_S") (pintype "passive"))
      (node (ref "Q4") (pin "D") (pinfunction "D_D") (pintype "passive"))
      (node (ref "R53") (pin "2") (pinfunction "2_2") (pintype "passive"))
      (node (ref "U$3") (pin "14") (pinfunction "OUT_14") (pintype "bidirectional"))
    )
    (net (code "107") (name "Net-(U$3-RFMIN)") (class "Default")
      (node (ref "RF_MAX") (pin "2") (pinfunction "2_2") (pintype "passive"))
      (node (ref "RF_MIN") (pin "2") (pinfunction "2_2") (pintype "passive"))
      (node (ref "R_SS") (pin "2") (pinfunction "2_2") (pintype "passive"))
      (node (ref "U$3") (pin "4") (pinfunction "RFMIN_4") (pintype "bidirectional"))
    )
    (net (code "108") (name "Net-(U$3-VBOOT)") (class "Default")
      (node (ref "C_BOOT") (pin "1") (pinfunction "1_1") (pintype "passive"))
      (node (ref "U$3") (pin "16") (pinfunction "VBOOT_16") (pintype "bidirectional"))
    )
    (net (code "109") (name "Net-(U$5-ANODE)") (class "Default")
      (node (ref "R14") (pin "2") (pinfunction "2_2") (pintype "passive"))
      (node (ref "U$5") (pin "2") (pinfunction "ANODE_2") (pintype "bidirectional"))
    )
    (net (code "110") (name "Net-(U$6-ANODE)") (class "Default")
      (node (ref "R17") (pin "1") (pinfunction "1_1") (pintype "passive"))
      (node (ref "U$6") (pin "2") (pinfunction "ANODE_2") (pintype "bidirectional"))
    )
    (net (code "111") (name "Net-(U3-CB)") (class "Default")
      (node (ref "C19") (pin "1") (pinfunction "1_1") (pintype "passive"))
      (node (ref "U3") (pin "1") (pinfunction "CB_1") (pintype "input"))
    )
    (net (code "112") (name "Net-(U4-CB)") (class "Default")
      (node (ref "C22") (pin "1") (pinfunction "1_1") (pintype "passive"))
      (node (ref "U4") (pin "1") (pinfunction "CB_1") (pintype "input"))
    )
    (net (code "113") (name "Net-(VR1-C)") (class "Default")
      (node (ref "LED1") (pin "C") (pinfunction "C_C") (pintype "passive"))
      (node (ref "VR1") (pin "1") (pinfunction "C_1") (pintype "passive"))
    )
    (net (code "114") (name "Net-(VR1-R)") (class "Default")
      (node (ref "R33") (pin "1") (pinfunction "1_1") (pintype "passive"))
      (node (ref "R36") (pin "2") (pinfunction "2_2") (pintype "passive"))
      (node (ref "VR1") (pin "2") (pinfunction "R_2") (pintype "passive"))
    )
    (net (code "115") (name "Net-(VR2-C)") (class "Default")
      (node (ref "LED2") (pin "C") (pinfunction "C_C") (pintype "passive"))
      (node (ref "VR2") (pin "1") (pinfunction "C_1") (pintype "passive"))
    )
    (net (code "116") (name "Net-(VR2-R)") (class "Default")
      (node (ref "R34") (pin "1") (pinfunction "1_1") (pintype "passive"))
      (node (ref "R37") (pin "2") (pinfunction "2_2") (pintype "passive"))
      (node (ref "VR2") (pin "2") (pinfunction "R_2") (pintype "passive"))
    )
    (net (code "117") (name "Net-(VR3-C)") (class "Default")
      (node (ref "LED3") (pin "C") (pinfunction "C_C") (pintype "passive"))
      (node (ref "VR3") (pin "1") (pinfunction "C_1") (pintype "passive"))
    )
    (net (code "118") (name "Net-(VR3-R)") (class "Default")
      (node (ref "R35") (pin "1") (pinfunction "1_1") (pintype "passive"))
      (node (ref "R38") (pin "2") (pinfunction "2_2") (pintype "passive"))
      (node (ref "VR3") (pin "2") (pinfunction "R_2") (pintype "passive"))
    )
    (net (code "119") (name "Net-(X1A-KL)") (class "Default")
      (node (ref "F1") (pin "2") (pinfunction "2_2") (pintype "passive"))
      (node (ref "R59") (pin "2") (pinfunction "2_2") (pintype "passive"))
      (node (ref "X1") (pin "1") (pinfunction "KL_1") (pintype "passive"))
    )
    (net (code "120") (name "OC0A{slash}MOSI_A") (class "Default")
      (node (ref "JP4") (pin "1") (pinfunction "1_1") (pintype "passive"))
      (node (ref "SV1") (pin "1") (pinfunction "1_1") (pintype "passive"))
      (node (ref "U$2") (pin "2") (pinfunction "(MOSI_A/TXD)PD3_2") (pintype "bidirectional"))
    )
    (net (code "121") (name "OC1A_FREQ{slash}MISO_A") (class "Default")
      (node (ref "R48") (pin "1") (pinfunction "1_1") (pintype "passive"))
      (node (ref "SV1") (pin "9") (pinfunction "9_9") (pintype "passive"))
      (node (ref "U$2") (pin "1") (pinfunction "(MISO_A)PD2_1") (pintype "bidirectional"))
    )
    (net (code "122") (name "RESET_NOTAUS") (class "Default")
      (node (ref "IC2") (pin "11") (pinfunction "R2_11") (pintype "input"))
      (node (ref "IC2") (pin "15") (pinfunction "R3_15") (pintype "input"))
      (node (ref "U$2") (pin "24") (pinfunction "PB4_24") (pintype "bidirectional"))
    )
    (net (code "123") (name "RST") (class "Default")
      (node (ref "SV1") (pin "5") (pinfunction "5_5") (pintype "passive"))
      (node (ref "U$2") (pin "31") (pinfunction "PE0(RESET)_31") (pintype "input"))
    )
    (net (code "124") (name "RST_ETH") (class "Default")
      (node (ref "U$2") (pin "32") (pinfunction "PD1_32") (pintype "bidirectional"))
      (node (ref "U1") (pin "14") (pinfunction "B6_14") (pintype "bidirectional"))
    )
    (net (code "125") (name "RST_ETH_3V") (class "Default")
      (node (ref "JP2") (pin "3") (pinfunction "3_3") (pintype "passive"))
      (node (ref "U1") (pin "7") (pinfunction "A6_7") (pintype "bidirectional"))
    )
    (net (code "126") (name "SCK") (class "Default")
      (node (ref "U$2") (pin "28") (pinfunction "(SCK)PB7_28") (pintype "bidirectional"))
      (node (ref "U1") (pin "15") (pinfunction "B5_15") (pintype "bidirectional"))
    )
    (net (code "127") (name "SCK_3V") (class "Default")
      (node (ref "JP1") (pin "1") (pinfunction "1_1") (pintype "passive"))
      (node (ref "U1") (pin "6") (pinfunction "A5_6") (pintype "bidirectional"))
    )
    (net (code "128") (name "SERVO_PWM") (class "Default")
      (node (ref "JP3") (pin "1") (pinfunction "1_1") (pintype "passive"))
      (node (ref "U$2") (pin "3") (pinfunction "PC1_3") (pintype "bidirectional"))
    )
    (net (code "129") (name "STBY") (class "Default")
      (node (ref "C12") (pin "1") (pinfunction "1_1") (pintype "passive"))
      (node (ref "R57") (pin "2") (pinfunction "2_2") (pintype "passive"))
      (node (ref "U$3") (pin "5") (pinfunction "STBY_5") (pintype "bidirectional"))
      (node (ref "U2") (pin "3") (pinfunction "2Y_3") (pintype "output"))
    )
    (net (code "130") (name "TASTER") (class "Default")
      (node (ref "C33") (pin "1") (pinfunction "1_1") (pintype "passive"))
      (node (ref "IC2") (pin "14") (pinfunction "S3_14") (pintype "input"))
      (node (ref "R22") (pin "2") (pinfunction "2_2") (pintype "passive"))
      (node (ref "S1") (pin "3") (pinfunction "P_3") (pintype "passive"))
      (node (ref "S1") (pin "4") (pinfunction "P1_4") (pintype "passive"))
    )
    (net (code "131") (name "WOL_ETH") (class "Default")
      (node (ref "U1") (pin "18") (pinfunction "B2_18") (pintype "bidirectional"))
    )
    (net (code "132") (name "WOL_ETH_3V") (class "Default")
      (node (ref "JP1") (pin "4") (pinfunction "4_4") (pintype "passive"))
      (node (ref "U1") (pin "3") (pinfunction "A2_3") (pintype "bidirectional"))
    )
    (net (code "133") (name "unconnected-(IC2A-Q0-Pad2)") (class "Default")
      (node (ref "IC2") (pin "2") (pinfunction "Q0_2") (pintype "output"))
    )
    (net (code "134") (name "unconnected-(IC2A-Q1-Pad9)") (class "Default")
      (node (ref "IC2") (pin "9") (pinfunction "Q1_9") (pintype "output"))
    )
    (net (code "135") (name "unconnected-(IC4B-OUT-Pad7)") (class "Default")
      (node (ref "IC4") (pin "7") (pinfunction "OUT_7") (pintype "output"))
    )
    (net (code "136") (name "unconnected-(L7-2-Pad8)") (class "Default")
      (node (ref "L7") (pin "8") (pinfunction "2_8") (pintype "passive"))
    )
    (net (code "137") (name "unconnected-(L7-3-Pad10)") (class "Default")
      (node (ref "L7") (pin "10") (pinfunction "3_10") (pintype "passive"))
    )
    (net (code "138") (name "unconnected-(L7-7-Pad5)") (class "Default")
      (node (ref "L7") (pin "5") (pinfunction "7_5") (pintype "passive"))
    )
    (net (code "139") (name "unconnected-(L7-Pad6)") (class "Default")
      (node (ref "L7") (pin "6") (pinfunction "6_6") (pintype "passive"))
    )
    (net (code "140") (name "unconnected-(OK2B-A-Pad3)") (class "Default")
      (node (ref "OK2") (pin "3") (pinfunction "A_3") (pintype "passive"))
    )
    (net (code "141") (name "unconnected-(OK2B-C-Pad4)") (class "Default")
      (node (ref "OK2") (pin "4") (pinfunction "C_4") (pintype "passive"))
    )
    (net (code "142") (name "unconnected-(OK2B-COL-Pad6)") (class "Default")
      (node (ref "OK2") (pin "6") (pinfunction "COL_6") (pintype "passive"))
    )
    (net (code "143") (name "unconnected-(OK2B-EMIT-Pad5)") (class "Default")
      (node (ref "OK2") (pin "5") (pinfunction "EMIT_5") (pintype "passive"))
    )
    (net (code "144") (name "unconnected-(RJ_1-PadP$1)") (class "Default")
      (node (ref "RJ_1") (pin "P$1") (pinfunction "P$1_P$1") (pintype "bidirectional"))
    )
    (net (code "145") (name "unconnected-(RJ_2-PadP$1)") (class "Default")
      (node (ref "RJ_2") (pin "P$1") (pinfunction "P$1_P$1") (pintype "bidirectional"))
    )
    (net (code "146") (name "unconnected-(SV1-Pad3)") (class "Default")
      (node (ref "SV1") (pin "3") (pinfunction "3_3") (pintype "passive"))
    )
    (net (code "147") (name "unconnected-(U$1-VREF-Pad5)") (class "Default")
      (node (ref "U$1") (pin "5") (pinfunction "VREF_5") (pintype "output"))
    )
    (net (code "148") (name "unconnected-(U$3-NC-Pad13)") (class "Default")
      (node (ref "U$3") (pin "13") (pinfunction "NC_13") (pintype "bidirectional"))
    )
    (net (code "149") (name "unconnected-(U$3-PFC_STOP-Pad9)") (class "Default")
      (node (ref "U$3") (pin "9") (pinfunction "PFC_STOP_9") (pintype "bidirectional"))
    )
    (net (code "150") (name "unconnected-(U$4-0V-Pad5)") (class "Default")
      (node (ref "U$4") (pin "5") (pinfunction "0V_5") (pintype "bidirectional"))
    )
    (net (code "151") (name "unconnected-(U3-NC-Pad3)") (class "Default")
      (node (ref "U3") (pin "3") (pinfunction "NC_3") (pintype "no_connect"))
    )
    (net (code "152") (name "unconnected-(U3-NC_2-Pad2)") (class "Default")
      (node (ref "U3") (pin "2") (pinfunction "NC_2_2") (pintype "no_connect"))
    )
    (net (code "153") (name "unconnected-(U3-ON{slash}~{OFF}-Pad5)") (class "Default")
      (node (ref "U3") (pin "5") (pinfunction "ON/~{OFF}_5") (pintype "input"))
    )
    (net (code "154") (name "unconnected-(U4-NC-Pad3)") (class "Default")
      (node (ref "U4") (pin "3") (pinfunction "NC_3") (pintype "no_connect"))
    )
    (net (code "155") (name "unconnected-(U4-NC_2-Pad2)") (class "Default")
      (node (ref "U4") (pin "2") (pinfunction "NC_2_2") (pintype "no_connect"))
    )
    (net (code "156") (name "unconnected-(U4-ON{slash}~{OFF}-Pad5)") (class "Default")
      (node (ref "U4") (pin "5") (pinfunction "ON/~{OFF}_5") (pintype "input"))
    )
    (net (code "157") (name "ÜBERSPANNUNG") (class "Default")
      (node (ref "C24") (pin "1") (pinfunction "1_1") (pintype "passive"))
      (node (ref "C41") (pin "1") (pinfunction "1_1") (pintype "passive"))
      (node (ref "IC2") (pin "12") (pinfunction "S2_12") (pintype "input"))
      (node (ref "OK2") (pin "7") (pinfunction "EMIT_7") (pintype "passive"))
      (node (ref "R10") (pin "2") (pinfunction "2_2") (pintype "passive"))
    )
  )
)
